# metronome.net
KiCad netlist of a schematic drawn in EAGLE
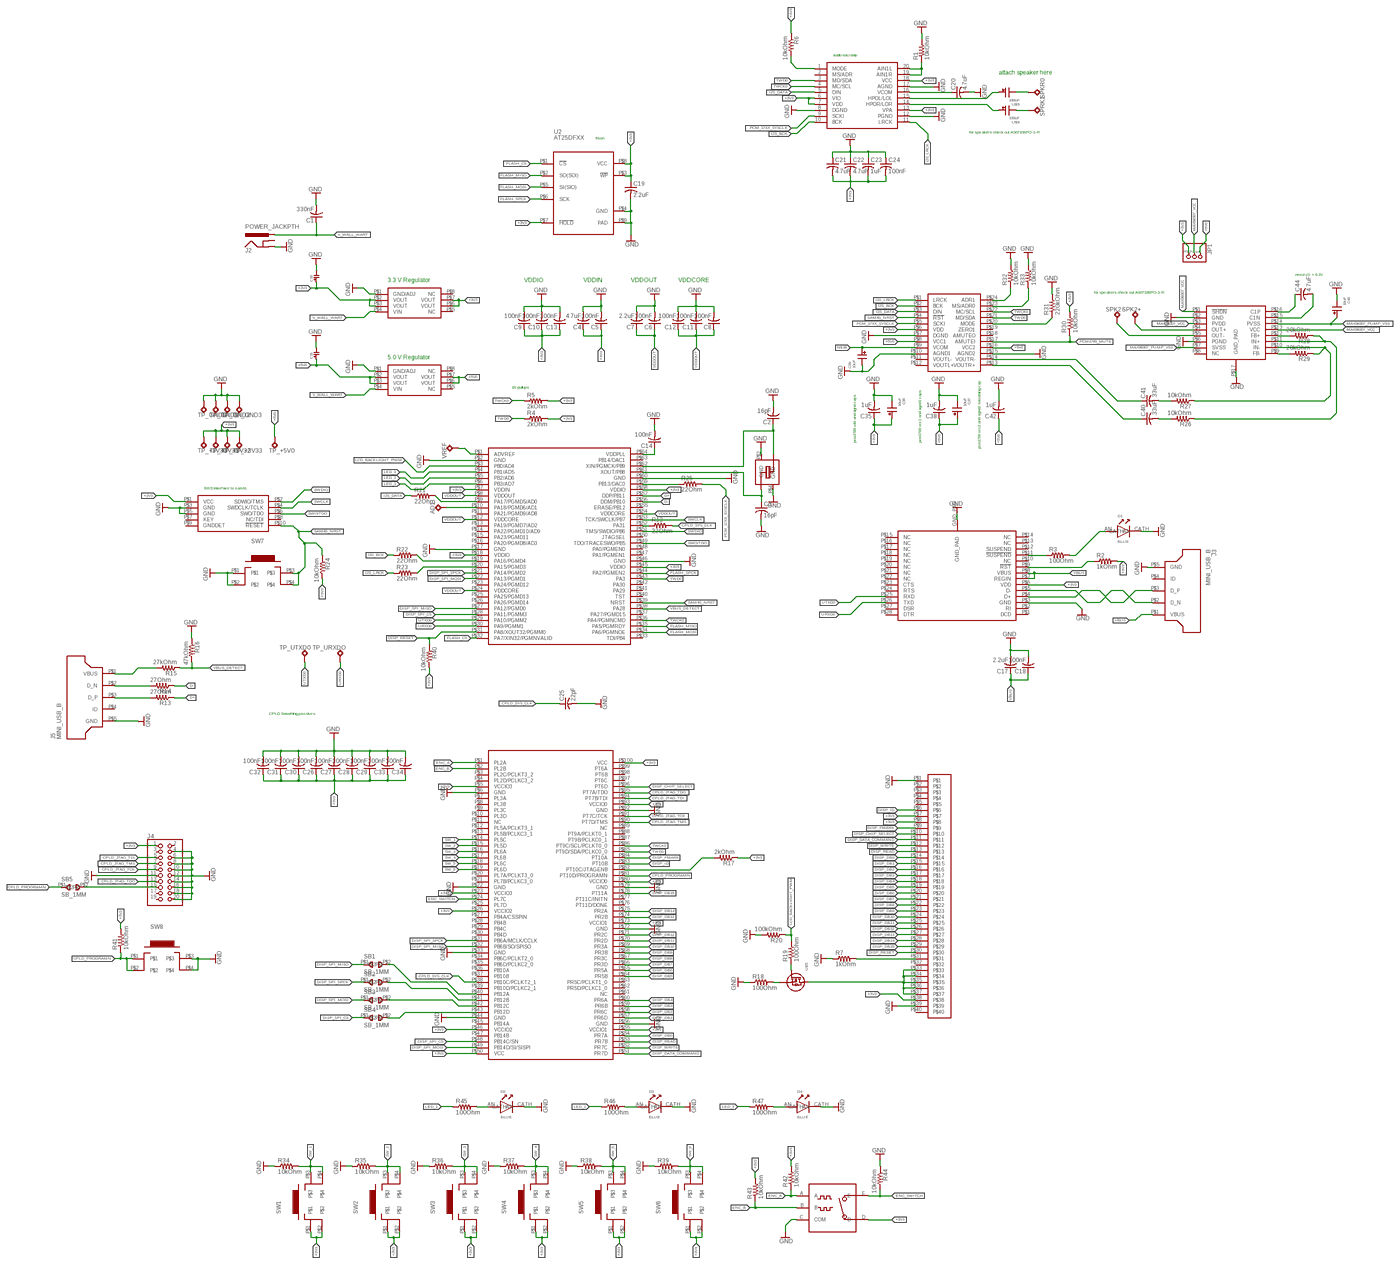
[diagram p0: schematic, sheet 1, overview]
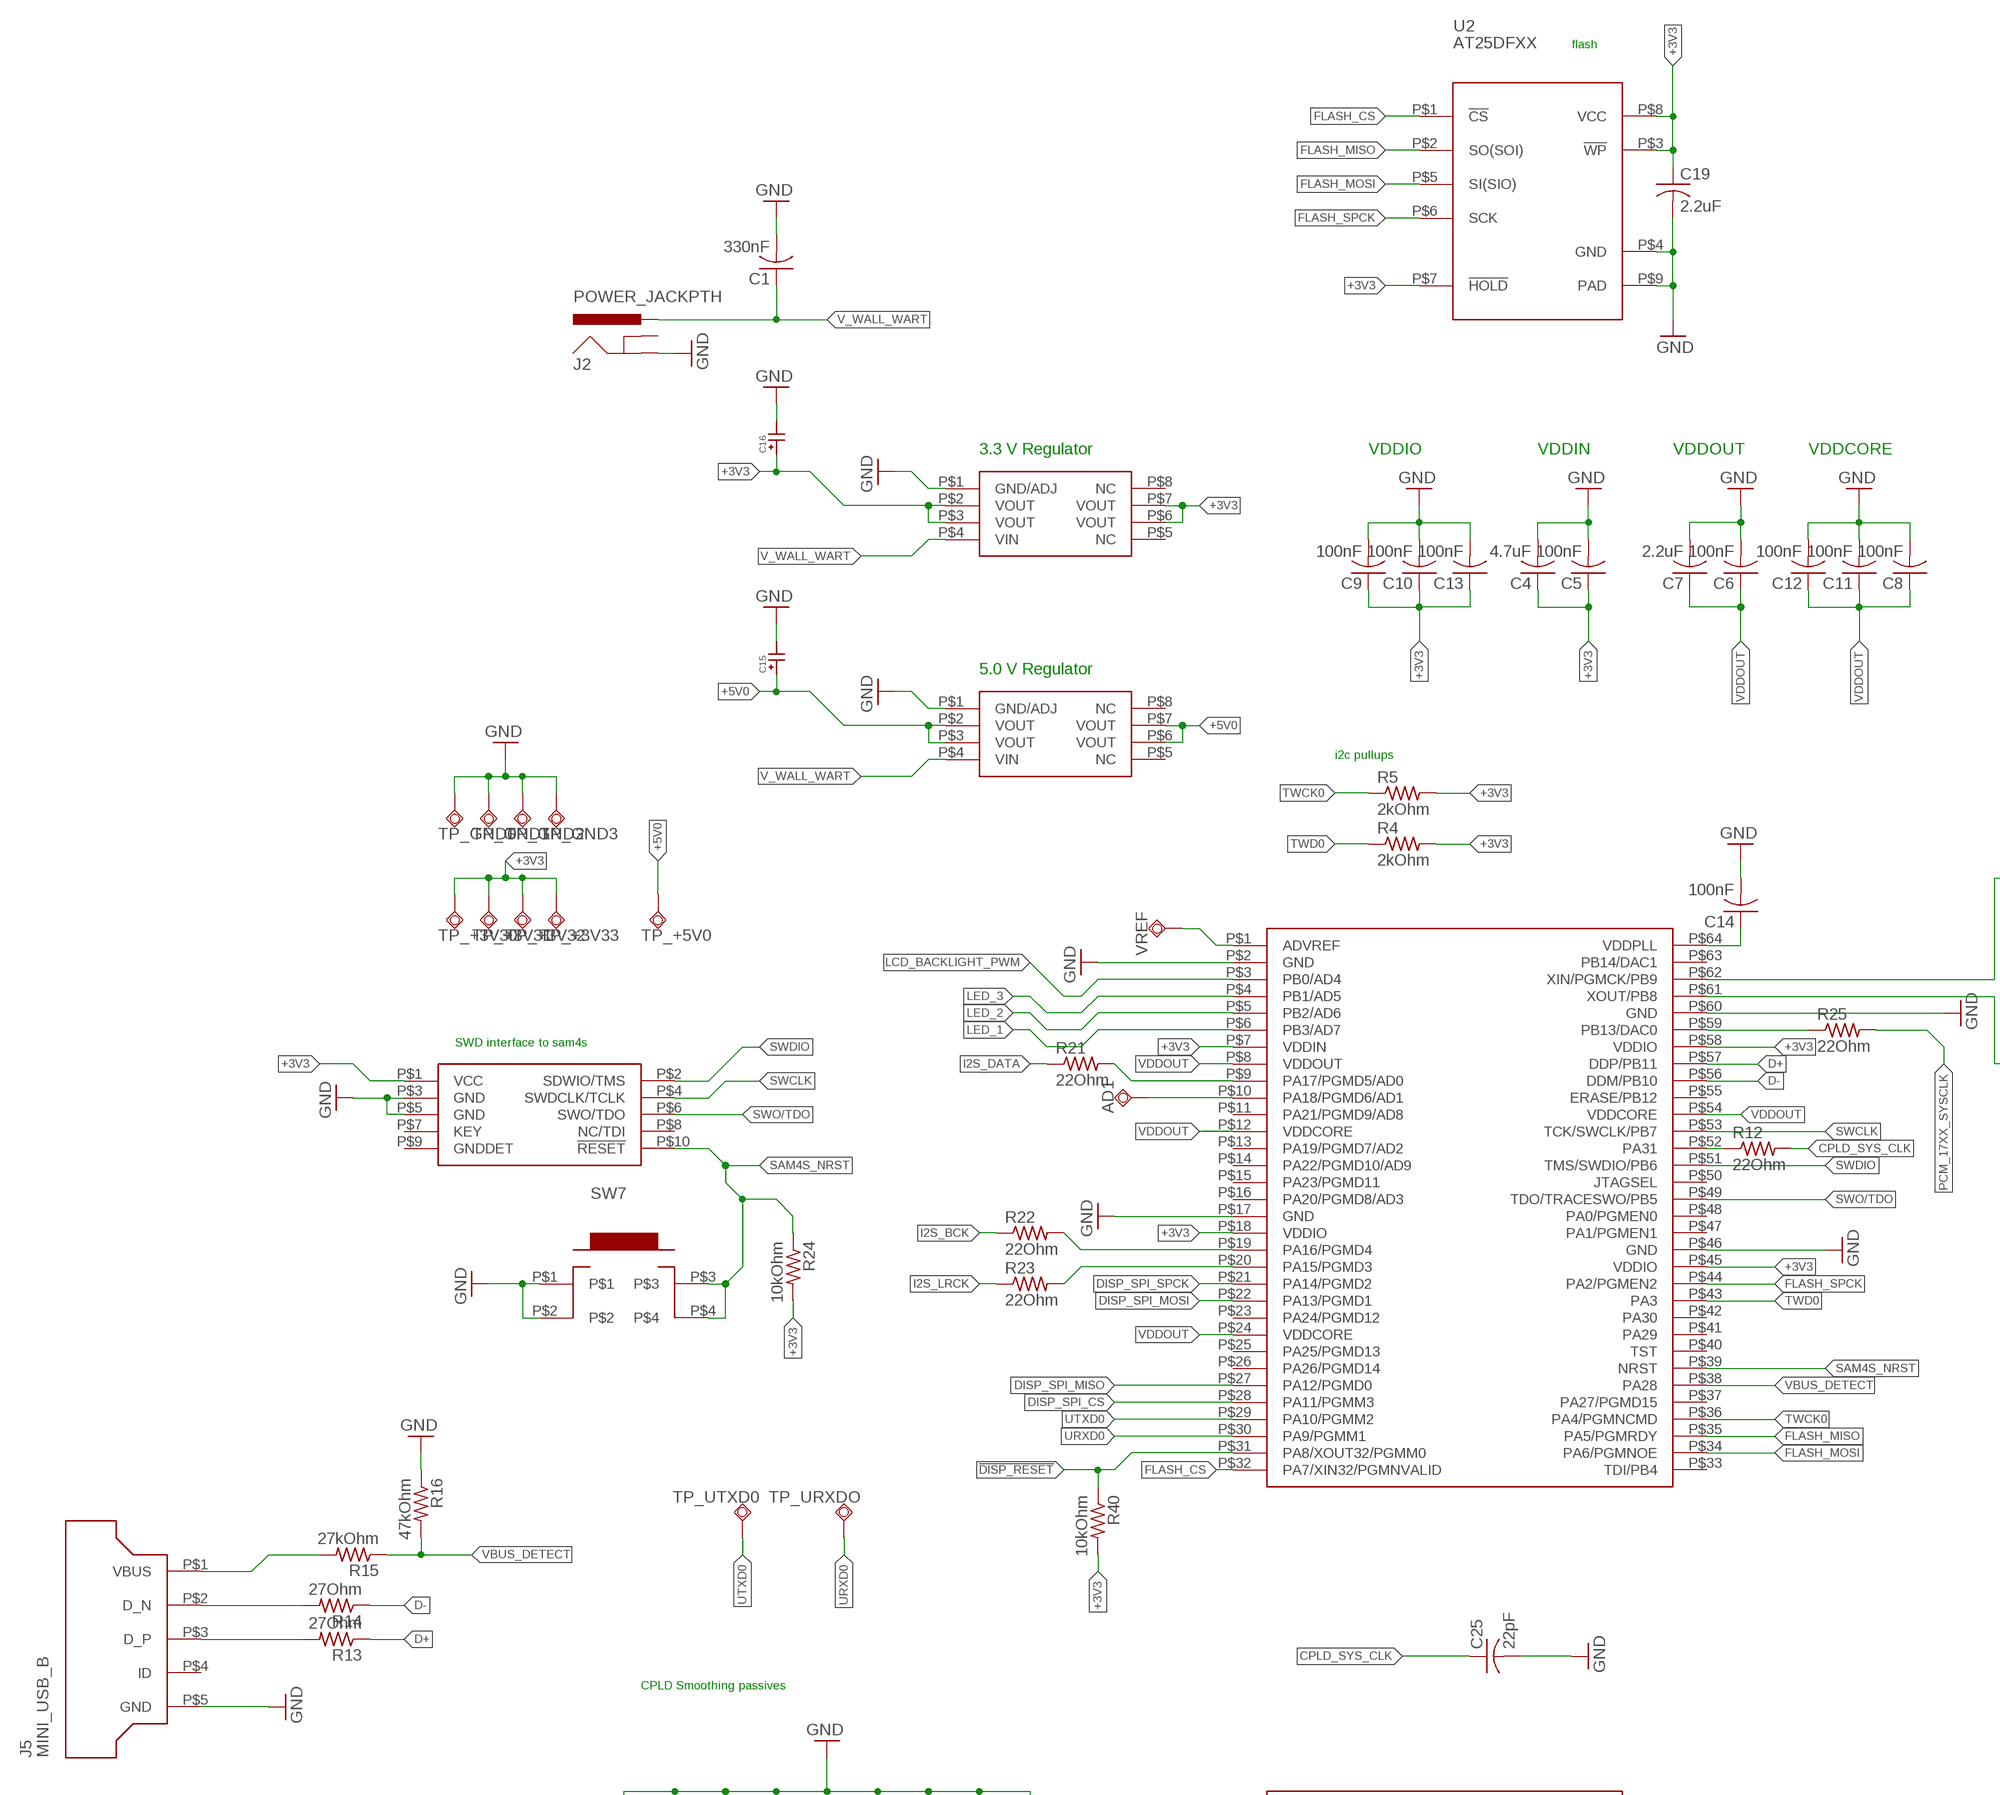
[diagram p1: schematic, sheet 1, part 1 of 4]
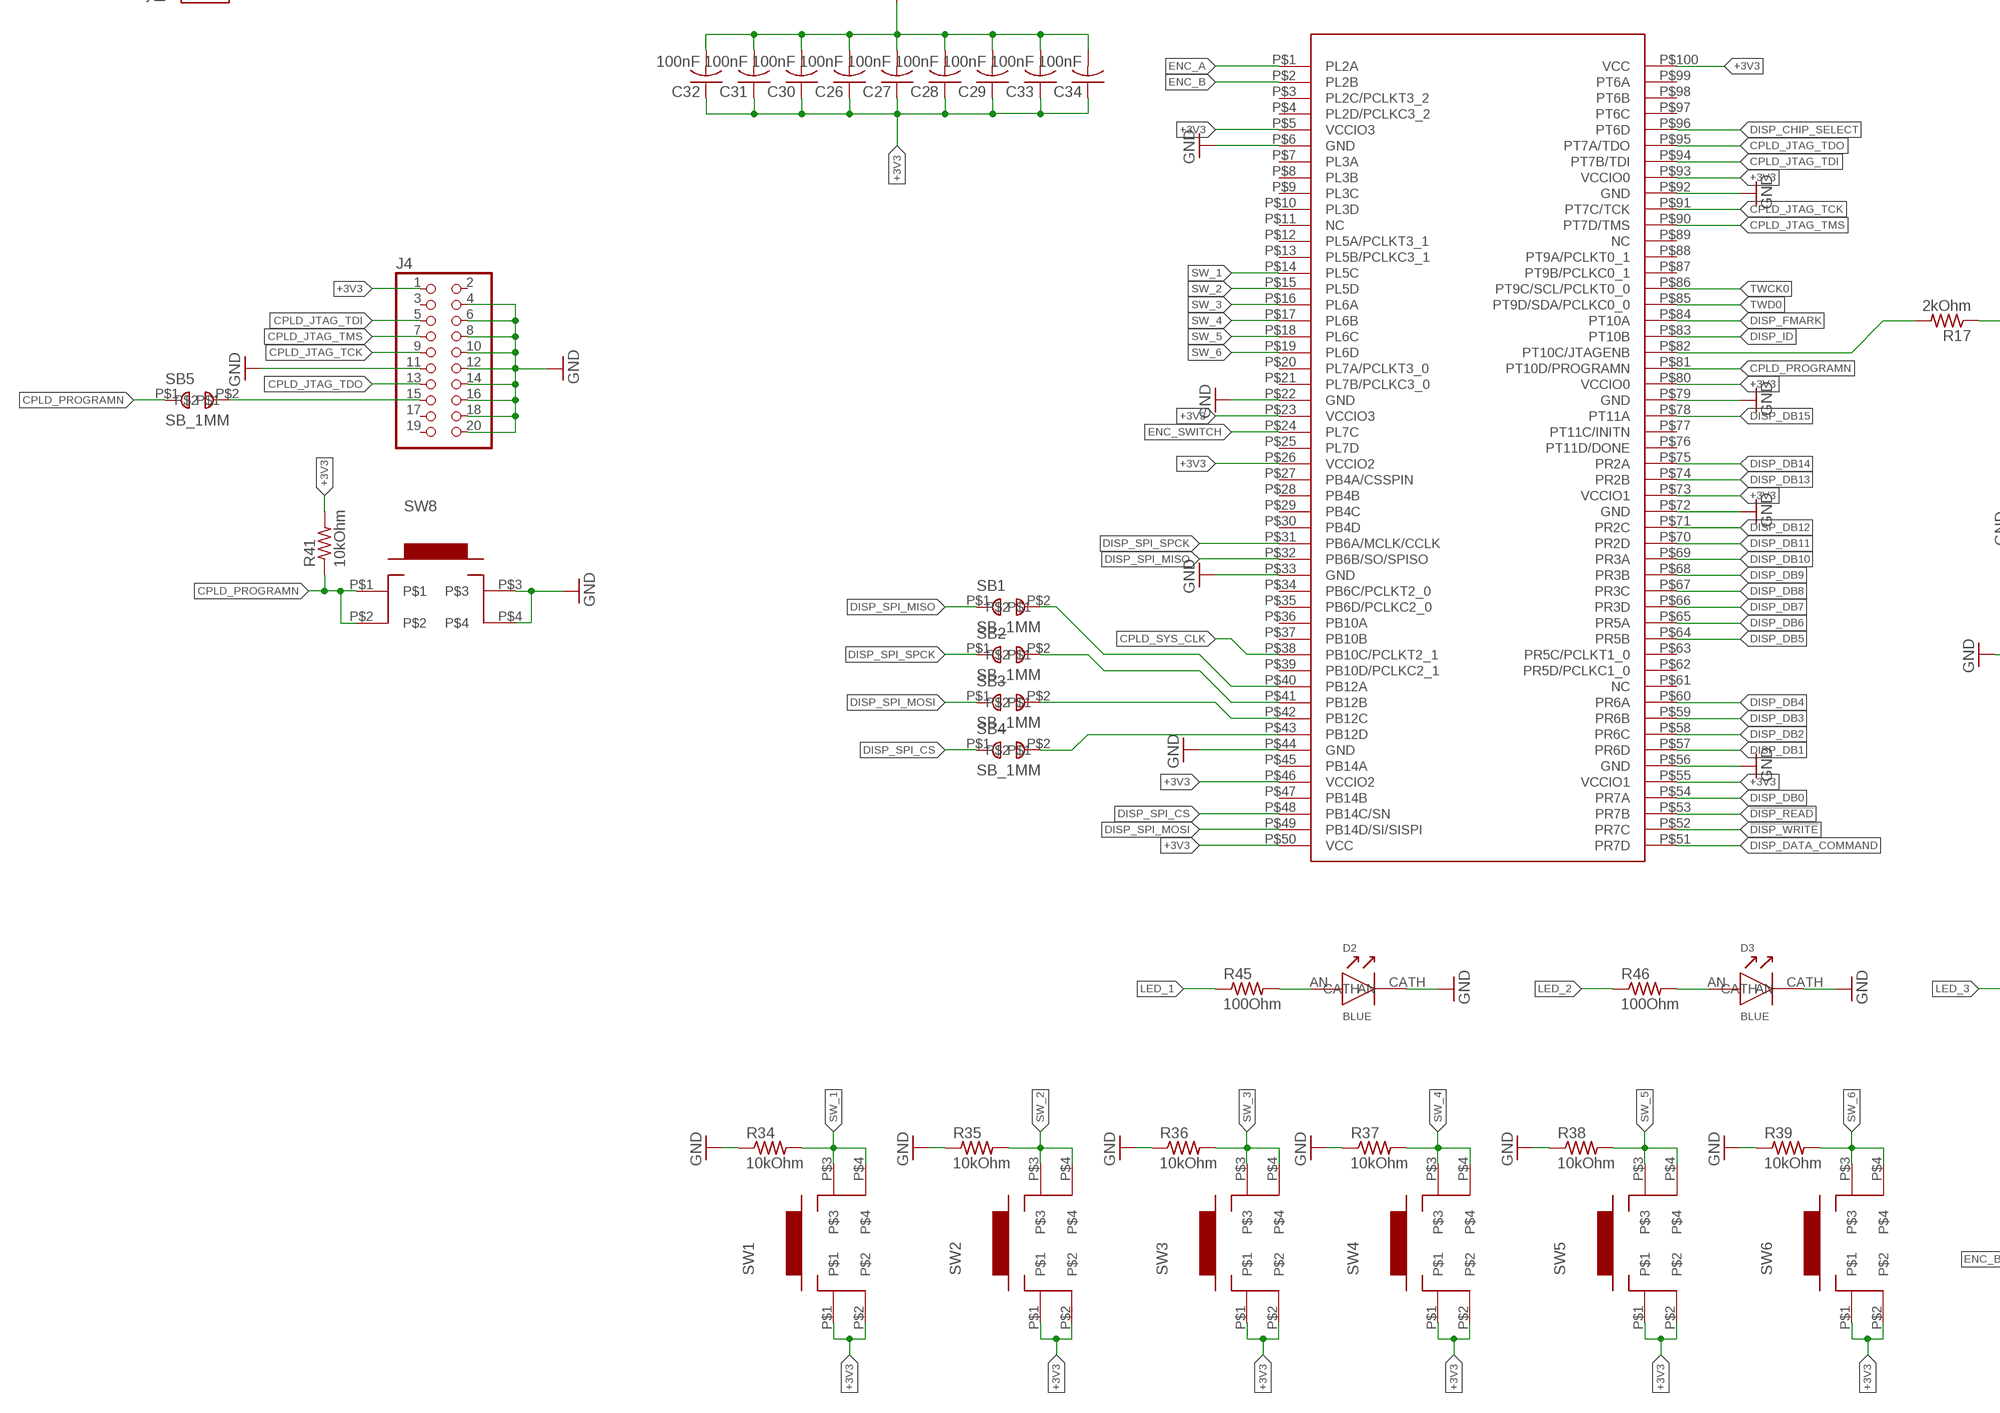
[diagram p2: schematic, sheet 1, part 2 of 4]
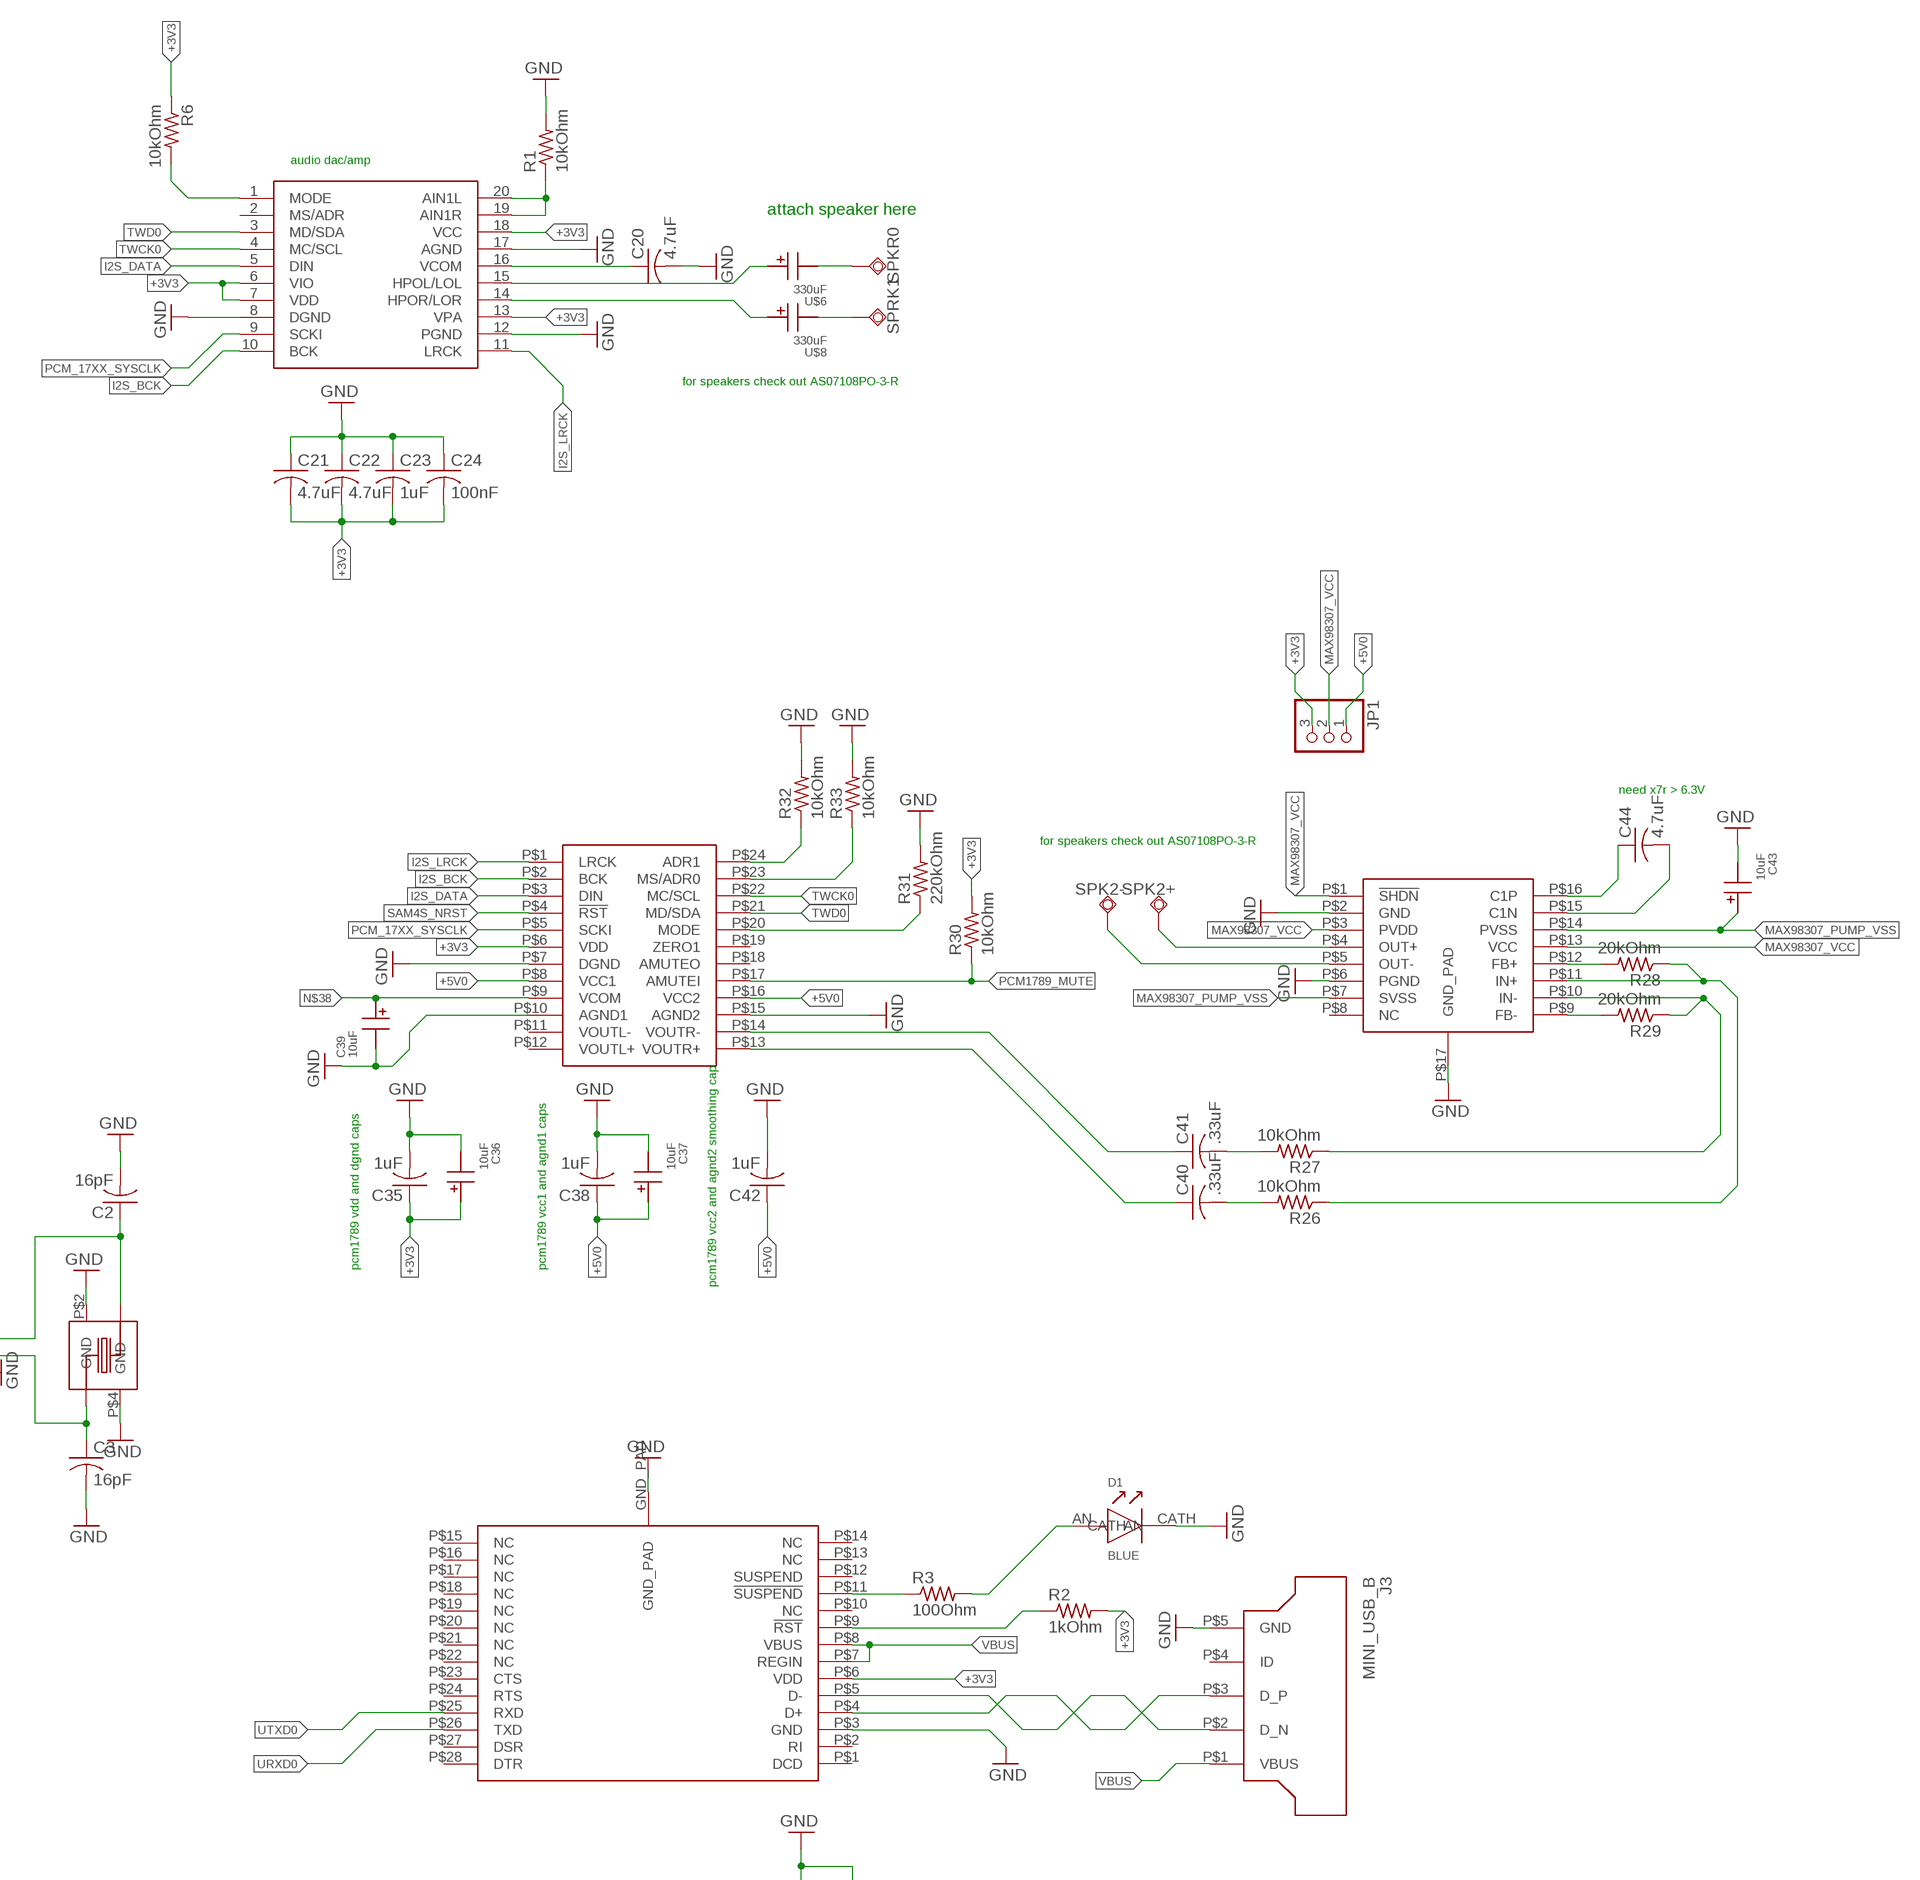
[diagram p3: schematic, sheet 1, part 3 of 4]
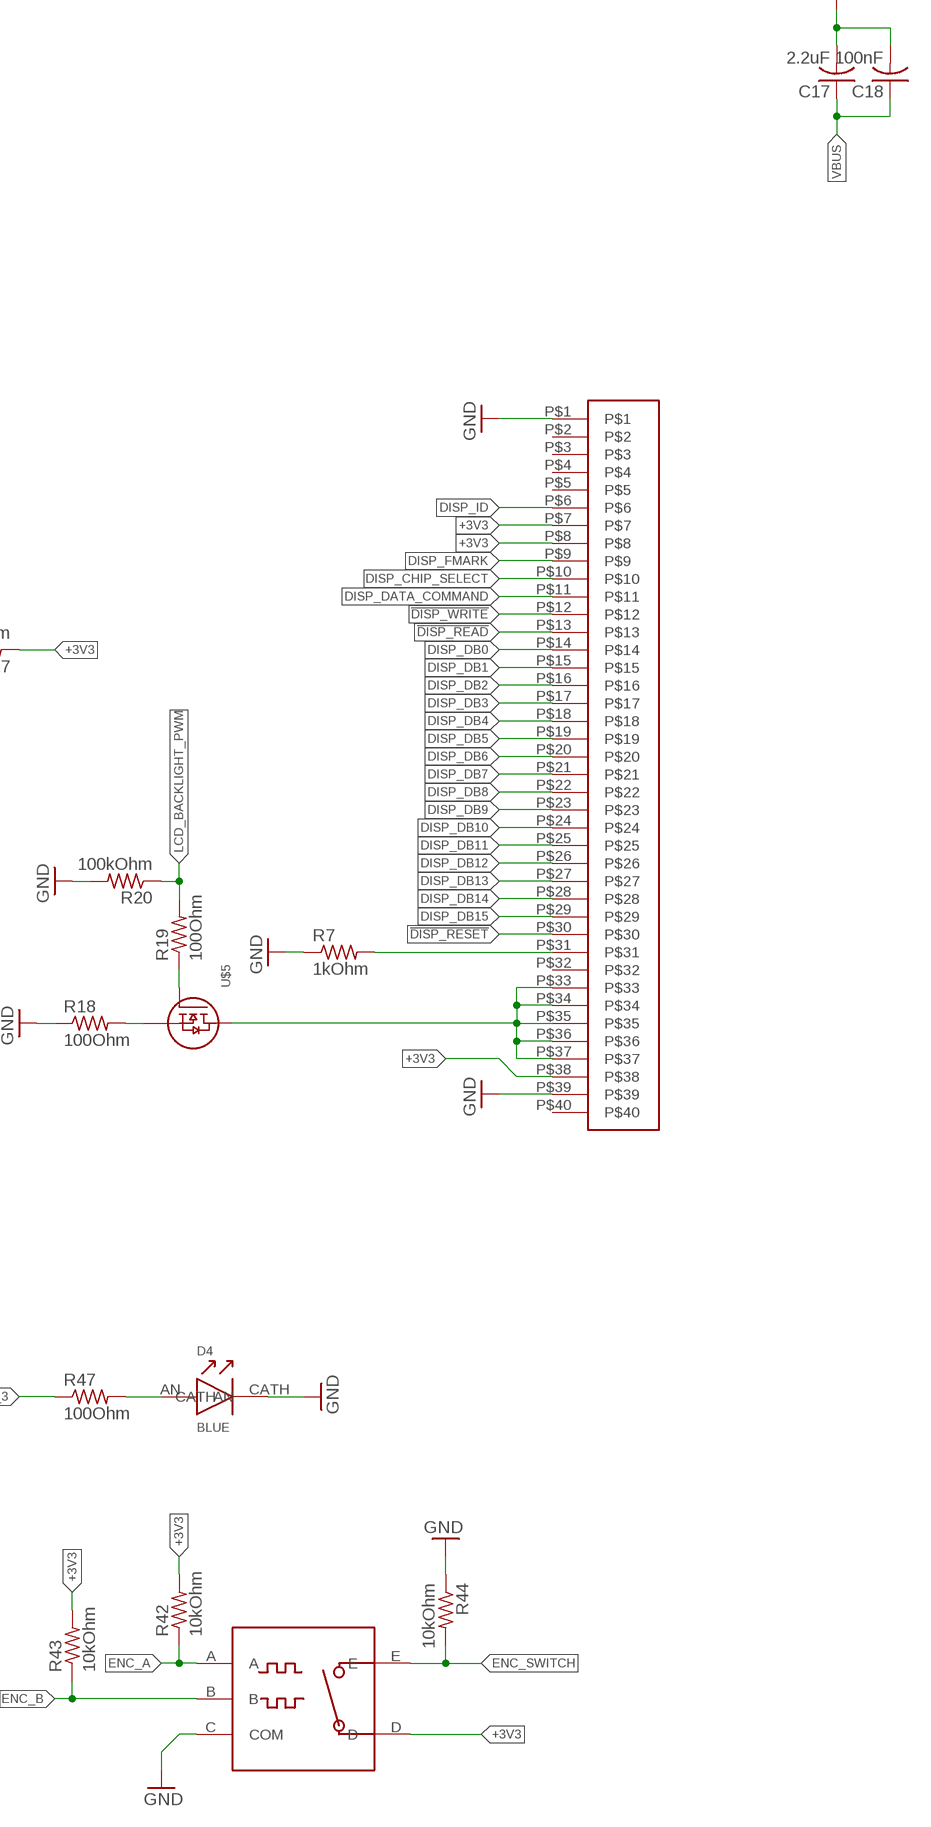
[diagram p4: schematic, sheet 1, part 4 of 4]

(export (version "E")
  (design (tool "Eeschema 10.0.6"))
  (components
    (comp (ref "3.3_V_REG")
      (value "MC33269D-3.3GOS-ND")
      (footprint "eagle-import:ON_SEMICONDUCTOR_MC33269")
      (libsource (lib "eagle-import") (part "MC33269D-3.3GOS-ND"))
    )
    (comp (ref "5.0_V_REG")
      (value "MC33269D-5.0GOS-ND")
      (footprint "eagle-import:ON_SEMICONDUCTOR_MC33269")
      (libsource (lib "eagle-import") (part "MC33269D-5.0GOS-ND"))
    )
    (comp (ref "AD1")
      (value "TPSQTP13SQ")
      (footprint "eagle-import:TP13SQ")
      (libsource (lib "eagle-import") (part "TPSQTP13SQ"))
    )
    (comp (ref "C1")
      (value "330nF")
      (footprint "eagle-import:C0402")
      (libsource (lib "eagle-import") (part "C-USC0402"))
    )
    (comp (ref "C2")
      (value "16pF")
      (footprint "eagle-import:C0402")
      (libsource (lib "eagle-import") (part "C-USC0402"))
    )
    (comp (ref "C3")
      (value "16pF")
      (footprint "eagle-import:C0402")
      (libsource (lib "eagle-import") (part "C-USC0402"))
    )
    (comp (ref "C4")
      (value "4.7uF")
      (footprint "eagle-import:C0603")
      (libsource (lib "eagle-import") (part "C-USC0603"))
    )
    (comp (ref "C5")
      (value "100nF")
      (footprint "eagle-import:C0402")
      (libsource (lib "eagle-import") (part "C-USC0402"))
    )
    (comp (ref "C6")
      (value "100nF")
      (footprint "eagle-import:C0402")
      (libsource (lib "eagle-import") (part "C-USC0402"))
    )
    (comp (ref "C7")
      (value "2.2uF")
      (footprint "eagle-import:C0603")
      (libsource (lib "eagle-import") (part "C-USC0603"))
    )
    (comp (ref "C8")
      (value "100nF")
      (footprint "eagle-import:C0402")
      (libsource (lib "eagle-import") (part "C-USC0402"))
    )
    (comp (ref "C9")
      (value "100nF")
      (footprint "eagle-import:C0402")
      (libsource (lib "eagle-import") (part "C-USC0402"))
    )
    (comp (ref "C10")
      (value "100nF")
      (footprint "eagle-import:C0402")
      (libsource (lib "eagle-import") (part "C-USC0402"))
    )
    (comp (ref "C11")
      (value "100nF")
      (footprint "eagle-import:C0402")
      (libsource (lib "eagle-import") (part "C-USC0402"))
    )
    (comp (ref "C12")
      (value "100nF")
      (footprint "eagle-import:C0402")
      (libsource (lib "eagle-import") (part "C-USC0402"))
    )
    (comp (ref "C13")
      (value "100nF")
      (footprint "eagle-import:C0402")
      (libsource (lib "eagle-import") (part "C-USC0402"))
    )
    (comp (ref "C14")
      (value "100nF")
      (footprint "eagle-import:C0402")
      (libsource (lib "eagle-import") (part "C-USC0402"))
    )
    (comp (ref "C15")
      (value "KEMET_T491A")
      (footprint "eagle-import:KEMET_T491A")
      (libsource (lib "eagle-import") (part "KEMET_T491A"))
    )
    (comp (ref "C16")
      (value "KEMET_T491A")
      (footprint "eagle-import:KEMET_T491A")
      (libsource (lib "eagle-import") (part "KEMET_T491A"))
    )
    (comp (ref "C17")
      (value "2.2uF")
      (footprint "eagle-import:C0603")
      (libsource (lib "eagle-import") (part "C-USC0603"))
    )
    (comp (ref "C18")
      (value "100nF")
      (footprint "eagle-import:C0402")
      (libsource (lib "eagle-import") (part "C-USC0402"))
    )
    (comp (ref "C19")
      (value "2.2uF")
      (footprint "eagle-import:C0603")
      (libsource (lib "eagle-import") (part "C-USC0603"))
    )
    (comp (ref "C20")
      (value "4.7uF")
      (footprint "eagle-import:C0402")
      (libsource (lib "eagle-import") (part "C-USC0402"))
    )
    (comp (ref "C21")
      (value "4.7uF")
      (footprint "eagle-import:C0402")
      (libsource (lib "eagle-import") (part "C-USC0402"))
    )
    (comp (ref "C22")
      (value "4.7uF")
      (footprint "eagle-import:C0402")
      (libsource (lib "eagle-import") (part "C-USC0402"))
    )
    (comp (ref "C23")
      (value "1uF")
      (footprint "eagle-import:C0402")
      (libsource (lib "eagle-import") (part "C-USC0402"))
    )
    (comp (ref "C24")
      (value "100nF")
      (footprint "eagle-import:C0402")
      (libsource (lib "eagle-import") (part "C-USC0402"))
    )
    (comp (ref "C25")
      (value "22pF")
      (footprint "eagle-import:C0402")
      (libsource (lib "eagle-import") (part "C-USC0402"))
    )
    (comp (ref "C26")
      (value "100nF")
      (footprint "eagle-import:C0402")
      (libsource (lib "eagle-import") (part "C-USC0402"))
    )
    (comp (ref "C27")
      (value "100nF")
      (footprint "eagle-import:C0402")
      (libsource (lib "eagle-import") (part "C-USC0402"))
    )
    (comp (ref "C28")
      (value "100nF")
      (footprint "eagle-import:C0402")
      (libsource (lib "eagle-import") (part "C-USC0402"))
    )
    (comp (ref "C29")
      (value "100nF")
      (footprint "eagle-import:C0402")
      (libsource (lib "eagle-import") (part "C-USC0402"))
    )
    (comp (ref "C30")
      (value "100nF")
      (footprint "eagle-import:C0402")
      (libsource (lib "eagle-import") (part "C-USC0402"))
    )
    (comp (ref "C31")
      (value "100nF")
      (footprint "eagle-import:C0402")
      (libsource (lib "eagle-import") (part "C-USC0402"))
    )
    (comp (ref "C32")
      (value "100nF")
      (footprint "eagle-import:C0402")
      (libsource (lib "eagle-import") (part "C-USC0402"))
    )
    (comp (ref "C33")
      (value "100nF")
      (footprint "eagle-import:C0402")
      (libsource (lib "eagle-import") (part "C-USC0402"))
    )
    (comp (ref "C34")
      (value "100nF")
      (footprint "eagle-import:C0402")
      (libsource (lib "eagle-import") (part "C-USC0402"))
    )
    (comp (ref "C35")
      (value "1uF")
      (footprint "eagle-import:C0402")
      (libsource (lib "eagle-import") (part "C-USC0402"))
    )
    (comp (ref "C36")
      (value "10uF")
      (footprint "eagle-import:PANASONIC_EEEHB100AR")
      (libsource (lib "eagle-import") (part "PANASONIC_HB1C100AR"))
    )
    (comp (ref "C37")
      (value "10uF")
      (footprint "eagle-import:PANASONIC_EEEHB100AR")
      (libsource (lib "eagle-import") (part "PANASONIC_HB1C100AR"))
    )
    (comp (ref "C38")
      (value "1uF")
      (footprint "eagle-import:C0402")
      (libsource (lib "eagle-import") (part "C-USC0402"))
    )
    (comp (ref "C39")
      (value "10uF")
      (footprint "eagle-import:PANASONIC_EEEHB100AR")
      (libsource (lib "eagle-import") (part "PANASONIC_HB1C100AR"))
    )
    (comp (ref "C40")
      (value ".33uF")
      (footprint "eagle-import:C0402")
      (libsource (lib "eagle-import") (part "C-USC0402"))
    )
    (comp (ref "C41")
      (value ".33uF")
      (footprint "eagle-import:C0402")
      (libsource (lib "eagle-import") (part "C-USC0402"))
    )
    (comp (ref "C42")
      (value "1uF")
      (footprint "eagle-import:C0402")
      (libsource (lib "eagle-import") (part "C-USC0402"))
    )
    (comp (ref "C43")
      (value "10uF")
      (footprint "eagle-import:PANASONIC_EEEHB100AR")
      (libsource (lib "eagle-import") (part "PANASONIC_HB1C100AR"))
    )
    (comp (ref "C44")
      (value "4.7uF")
      (footprint "eagle-import:C0603")
      (libsource (lib "eagle-import") (part "C-USC0603"))
    )
    (comp (ref "D1")
      (value "BLUE")
      (footprint "eagle-import:D0603")
      (libsource (lib "eagle-import") (part "LED0603"))
    )
    (comp (ref "D2")
      (value "BLUE")
      (footprint "eagle-import:D0603")
      (libsource (lib "eagle-import") (part "LED0603"))
    )
    (comp (ref "D3")
      (value "BLUE")
      (footprint "eagle-import:D0603")
      (libsource (lib "eagle-import") (part "LED0603"))
    )
    (comp (ref "D4")
      (value "BLUE")
      (footprint "eagle-import:D0603")
      (libsource (lib "eagle-import") (part "LED0603"))
    )
    (comp (ref "J1")
      (value "FCI_CORTEX_SWD_CONNECTOR")
      (footprint "eagle-import:FCI_10_PIN_SMD_0.5")
      (libsource (lib "eagle-import") (part "FCI_CORTEX_SWD_CONNECTOR"))
    )
    (comp (ref "J2")
      (value "POWER_JACKPTH")
      (footprint "eagle-import:POWER_JACK_PTH")
      (libsource (lib "eagle-import") (part "POWER_JACKPTH"))
    )
    (comp (ref "J3")
      (value "MINI_USB_B")
      (footprint "eagle-import:UX60SC-MB-5ST")
      (libsource (lib "eagle-import") (part "MINI_USB_B"))
    )
    (comp (ref "J4")
      (value "PINHD-2X10")
      (footprint "eagle-import:2X10")
      (libsource (lib "eagle-import") (part "PINHD-2X10"))
    )
    (comp (ref "J5")
      (value "MINI_USB_B")
      (footprint "eagle-import:UX60SC-MB-5ST")
      (libsource (lib "eagle-import") (part "MINI_USB_B"))
    )
    (comp (ref "JP1")
      (value "PINHD-1X3")
      (footprint "eagle-import:1X03")
      (libsource (lib "eagle-import") (part "PINHD-1X3"))
    )
    (comp (ref "R1")
      (value "10kOhm")
      (footprint "eagle-import:R0402")
      (libsource (lib "eagle-import") (part "R-US_R0402"))
    )
    (comp (ref "R2")
      (value "1kOhm")
      (footprint "eagle-import:R0402")
      (libsource (lib "eagle-import") (part "R-US_R0402"))
    )
    (comp (ref "R3")
      (value "100Ohm")
      (footprint "eagle-import:R0402")
      (libsource (lib "eagle-import") (part "R-US_R0402"))
    )
    (comp (ref "R4")
      (value "2kOhm")
      (footprint "eagle-import:R0402")
      (libsource (lib "eagle-import") (part "R-US_R0402"))
    )
    (comp (ref "R5")
      (value "2kOhm")
      (footprint "eagle-import:R0402")
      (libsource (lib "eagle-import") (part "R-US_R0402"))
    )
    (comp (ref "R6")
      (value "10kOhm")
      (footprint "eagle-import:R0402")
      (libsource (lib "eagle-import") (part "R-US_R0402"))
    )
    (comp (ref "R7")
      (value "1kOhm")
      (footprint "eagle-import:R0402")
      (libsource (lib "eagle-import") (part "R-US_R0402"))
    )
    (comp (ref "R12")
      (value "22Ohm")
      (footprint "eagle-import:R0402")
      (libsource (lib "eagle-import") (part "R-US_R0402"))
    )
    (comp (ref "R13")
      (value "27Ohm")
      (footprint "eagle-import:R0402")
      (libsource (lib "eagle-import") (part "R-US_R0402"))
    )
    (comp (ref "R14")
      (value "27Ohm")
      (footprint "eagle-import:R0402")
      (libsource (lib "eagle-import") (part "R-US_R0402"))
    )
    (comp (ref "R15")
      (value "27kOhm")
      (footprint "eagle-import:R0402")
      (libsource (lib "eagle-import") (part "R-US_R0402"))
    )
    (comp (ref "R16")
      (value "47kOhm")
      (footprint "eagle-import:R0402")
      (libsource (lib "eagle-import") (part "R-US_R0402"))
    )
    (comp (ref "R17")
      (value "2kOhm")
      (footprint "eagle-import:R0402")
      (libsource (lib "eagle-import") (part "R-US_R0402"))
    )
    (comp (ref "R18")
      (value "100Ohm")
      (footprint "eagle-import:R0402")
      (libsource (lib "eagle-import") (part "R-US_R0402"))
    )
    (comp (ref "R19")
      (value "100Ohm")
      (footprint "eagle-import:R0402")
      (libsource (lib "eagle-import") (part "R-US_R0402"))
    )
    (comp (ref "R20")
      (value "100kOhm")
      (footprint "eagle-import:R0402")
      (libsource (lib "eagle-import") (part "R-US_R0402"))
    )
    (comp (ref "R21")
      (value "22Ohm")
      (footprint "eagle-import:R0402")
      (libsource (lib "eagle-import") (part "R-US_R0402"))
    )
    (comp (ref "R22")
      (value "22Ohm")
      (footprint "eagle-import:R0402")
      (libsource (lib "eagle-import") (part "R-US_R0402"))
    )
    (comp (ref "R23")
      (value "22Ohm")
      (footprint "eagle-import:R0402")
      (libsource (lib "eagle-import") (part "R-US_R0402"))
    )
    (comp (ref "R24")
      (value "10kOhm")
      (footprint "eagle-import:R0402")
      (libsource (lib "eagle-import") (part "R-US_R0402"))
    )
    (comp (ref "R25")
      (value "22Ohm")
      (footprint "eagle-import:R0402")
      (libsource (lib "eagle-import") (part "R-US_R0402"))
    )
    (comp (ref "R26")
      (value "10kOhm")
      (footprint "eagle-import:R0402")
      (libsource (lib "eagle-import") (part "R-US_R0402"))
    )
    (comp (ref "R27")
      (value "10kOhm")
      (footprint "eagle-import:R0402")
      (libsource (lib "eagle-import") (part "R-US_R0402"))
    )
    (comp (ref "R28")
      (value "20kOhm")
      (footprint "eagle-import:R0402")
      (libsource (lib "eagle-import") (part "R-US_R0402"))
    )
    (comp (ref "R29")
      (value "20kOhm")
      (footprint "eagle-import:R0402")
      (libsource (lib "eagle-import") (part "R-US_R0402"))
    )
    (comp (ref "R30")
      (value "10kOhm")
      (footprint "eagle-import:R0402")
      (libsource (lib "eagle-import") (part "R-US_R0402"))
    )
    (comp (ref "R31")
      (value "220kOhm")
      (footprint "eagle-import:R0402")
      (libsource (lib "eagle-import") (part "R-US_R0402"))
    )
    (comp (ref "R32")
      (value "10kOhm")
      (footprint "eagle-import:R0402")
      (libsource (lib "eagle-import") (part "R-US_R0402"))
    )
    (comp (ref "R33")
      (value "10kOhm")
      (footprint "eagle-import:R0402")
      (libsource (lib "eagle-import") (part "R-US_R0402"))
    )
    (comp (ref "R34")
      (value "10kOhm")
      (footprint "eagle-import:R0402")
      (libsource (lib "eagle-import") (part "R-US_R0402"))
    )
    (comp (ref "R35")
      (value "10kOhm")
      (footprint "eagle-import:R0402")
      (libsource (lib "eagle-import") (part "R-US_R0402"))
    )
    (comp (ref "R36")
      (value "10kOhm")
      (footprint "eagle-import:R0402")
      (libsource (lib "eagle-import") (part "R-US_R0402"))
    )
    (comp (ref "R37")
      (value "10kOhm")
      (footprint "eagle-import:R0402")
      (libsource (lib "eagle-import") (part "R-US_R0402"))
    )
    (comp (ref "R38")
      (value "10kOhm")
      (footprint "eagle-import:R0402")
      (libsource (lib "eagle-import") (part "R-US_R0402"))
    )
    (comp (ref "R39")
      (value "10kOhm")
      (footprint "eagle-import:R0402")
      (libsource (lib "eagle-import") (part "R-US_R0402"))
    )
    (comp (ref "R40")
      (value "10kOhm")
      (footprint "eagle-import:R0402")
      (libsource (lib "eagle-import") (part "R-US_R0402"))
    )
    (comp (ref "R41")
      (value "10kOhm")
      (footprint "eagle-import:R0402")
      (libsource (lib "eagle-import") (part "R-US_R0402"))
    )
    (comp (ref "R42")
      (value "10kOhm")
      (footprint "eagle-import:R0402")
      (libsource (lib "eagle-import") (part "R-US_R0402"))
    )
    (comp (ref "R43")
      (value "10kOhm")
      (footprint "eagle-import:R0402")
      (libsource (lib "eagle-import") (part "R-US_R0402"))
    )
    (comp (ref "R44")
      (value "10kOhm")
      (footprint "eagle-import:R0402")
      (libsource (lib "eagle-import") (part "R-US_R0402"))
    )
    (comp (ref "R45")
      (value "100Ohm")
      (footprint "eagle-import:R0402")
      (libsource (lib "eagle-import") (part "R-US_R0402"))
    )
    (comp (ref "R46")
      (value "100Ohm")
      (footprint "eagle-import:R0402")
      (libsource (lib "eagle-import") (part "R-US_R0402"))
    )
    (comp (ref "R47")
      (value "100Ohm")
      (footprint "eagle-import:R0402")
      (libsource (lib "eagle-import") (part "R-US_R0402"))
    )
    (comp (ref "SB1")
      (value "SB_1MM")
      (footprint "eagle-import:SB_1MM")
      (libsource (lib "eagle-import") (part "SB_1MM"))
    )
    (comp (ref "SB2")
      (value "SB_1MM")
      (footprint "eagle-import:SB_1MM")
      (libsource (lib "eagle-import") (part "SB_1MM"))
    )
    (comp (ref "SB3")
      (value "SB_1MM")
      (footprint "eagle-import:SB_1MM")
      (libsource (lib "eagle-import") (part "SB_1MM"))
    )
    (comp (ref "SB4")
      (value "SB_1MM")
      (footprint "eagle-import:SB_1MM")
      (libsource (lib "eagle-import") (part "SB_1MM"))
    )
    (comp (ref "SB5")
      (value "SB_1MM")
      (footprint "eagle-import:SB_1MM")
      (libsource (lib "eagle-import") (part "SB_1MM"))
    )
    (comp (ref "SPK2+")
      (value "TPSQTP20SQ")
      (footprint "eagle-import:TP20SQ")
      (libsource (lib "eagle-import") (part "TPSQTP20SQ"))
    )
    (comp (ref "SPK2-")
      (value "TPSQTP20SQ")
      (footprint "eagle-import:TP20SQ")
      (libsource (lib "eagle-import") (part "TPSQTP20SQ"))
    )
    (comp (ref "SPKR0")
      (value "TPSQTP20SQ")
      (footprint "eagle-import:TP20SQ")
      (libsource (lib "eagle-import") (part "TPSQTP20SQ"))
    )
    (comp (ref "SPRK1")
      (value "TPSQTP20SQ")
      (footprint "eagle-import:TP20SQ")
      (libsource (lib "eagle-import") (part "TPSQTP20SQ"))
    )
    (comp (ref "SW1")
      (value "FSMJSMA")
      (footprint "eagle-import:FSMJSMA")
      (libsource (lib "eagle-import") (part "FSMJSMA"))
    )
    (comp (ref "SW2")
      (value "FSMJSMA")
      (footprint "eagle-import:FSMJSMA")
      (libsource (lib "eagle-import") (part "FSMJSMA"))
    )
    (comp (ref "SW3")
      (value "FSMJSMA")
      (footprint "eagle-import:FSMJSMA")
      (libsource (lib "eagle-import") (part "FSMJSMA"))
    )
    (comp (ref "SW4")
      (value "FSMJSMA")
      (footprint "eagle-import:FSMJSMA")
      (libsource (lib "eagle-import") (part "FSMJSMA"))
    )
    (comp (ref "SW5")
      (value "FSMJSMA")
      (footprint "eagle-import:FSMJSMA")
      (libsource (lib "eagle-import") (part "FSMJSMA"))
    )
    (comp (ref "SW6")
      (value "FSMJSMA")
      (footprint "eagle-import:FSMJSMA")
      (libsource (lib "eagle-import") (part "FSMJSMA"))
    )
    (comp (ref "SW7")
      (value "FSMJSMA")
      (footprint "eagle-import:FSMJSMA")
      (libsource (lib "eagle-import") (part "FSMJSMA"))
    )
    (comp (ref "SW8")
      (value "FSMJSMA")
      (footprint "eagle-import:FSMJSMA")
      (libsource (lib "eagle-import") (part "FSMJSMA"))
    )
    (comp (ref "TP_+3V30")
      (value "TPSQTP20SQ")
      (footprint "eagle-import:TP20SQ")
      (libsource (lib "eagle-import") (part "TPSQTP20SQ"))
    )
    (comp (ref "TP_+3V31")
      (value "TPSQTP20SQ")
      (footprint "eagle-import:TP20SQ")
      (libsource (lib "eagle-import") (part "TPSQTP20SQ"))
    )
    (comp (ref "TP_+3V32")
      (value "TPSQTP20SQ")
      (footprint "eagle-import:TP20SQ")
      (libsource (lib "eagle-import") (part "TPSQTP20SQ"))
    )
    (comp (ref "TP_+3V33")
      (value "TPSQTP20SQ")
      (footprint "eagle-import:TP20SQ")
      (libsource (lib "eagle-import") (part "TPSQTP20SQ"))
    )
    (comp (ref "TP_+5V0")
      (value "TPSQTP20SQ")
      (footprint "eagle-import:TP20SQ")
      (libsource (lib "eagle-import") (part "TPSQTP20SQ"))
    )
    (comp (ref "TP_GND0")
      (value "TPSQTP20SQ")
      (footprint "eagle-import:TP20SQ")
      (libsource (lib "eagle-import") (part "TPSQTP20SQ"))
    )
    (comp (ref "TP_GND1")
      (value "TPSQTP20SQ")
      (footprint "eagle-import:TP20SQ")
      (libsource (lib "eagle-import") (part "TPSQTP20SQ"))
    )
    (comp (ref "TP_GND2")
      (value "TPSQTP20SQ")
      (footprint "eagle-import:TP20SQ")
      (libsource (lib "eagle-import") (part "TPSQTP20SQ"))
    )
    (comp (ref "TP_GND3")
      (value "TPSQTP20SQ")
      (footprint "eagle-import:TP20SQ")
      (libsource (lib "eagle-import") (part "TPSQTP20SQ"))
    )
    (comp (ref "TP_URXDO")
      (value "TPSQTP20SQ")
      (footprint "eagle-import:TP20SQ")
      (libsource (lib "eagle-import") (part "TPSQTP20SQ"))
    )
    (comp (ref "TP_UTXD0")
      (value "TPSQTP20SQ")
      (footprint "eagle-import:TP20SQ")
      (libsource (lib "eagle-import") (part "TPSQTP20SQ"))
    )
    (comp (ref "U$1")
      (value "LATTICE_LCMXO2-640HC-4TG100C")
      (footprint "eagle-import:LATTICE_MACHXO_TQFP100")
      (libsource (lib "eagle-import") (part "LATTICE_LCMXO2-640HC-4TG100C"))
    )
    (comp (ref "U$2")
      (value "TI_PCM1774")
      (footprint "eagle-import:TI_QFN_20")
      (libsource (lib "eagle-import") (part "TI_PCM1774"))
    )
    (comp (ref "U$3")
      (value "ECS_ECS-120-20-33-CKM-TR")
      (footprint "eagle-import:ECS_ECX-32")
      (libsource (lib "eagle-import") (part "ECS_ECS-120-20-33-CKM-TR"))
    )
    (comp (ref "U$4")
      (value "40_PIN_MOLEX_FFC")
      (footprint "eagle-import:40_PIN_MOLEX_FFC")
      (libsource (lib "eagle-import") (part "40_PIN_MOLEX_FFC"))
    )
    (comp (ref "U$5")
      (value "DIODES_INCORPORATED_2N7002-7-F")
      (footprint "eagle-import:DIODES_INCORPORATED_SOT23")
      (libsource (lib "eagle-import") (part "DIODES_INCORPORATED_2N7002-7-F"))
    )
    (comp (ref "U$6")
      (value "330uF")
      (footprint "eagle-import:PANASONIC_EEEFT0JXXX")
      (libsource (lib "eagle-import") (part "PANASONIC_EEEFT0JXXX"))
    )
    (comp (ref "U$7")
      (value "SILABS_CP2102")
      (footprint "eagle-import:SILABS_QFN28")
      (libsource (lib "eagle-import") (part "SILABS_CP2102"))
    )
    (comp (ref "U$8")
      (value "330uF")
      (footprint "eagle-import:PANASONIC_EEEFT0JXXX")
      (libsource (lib "eagle-import") (part "PANASONIC_EEEFT0JXXX"))
    )
    (comp (ref "U$9")
      (value "TI_PCM1789")
      (footprint "eagle-import:TI_PW_TSSOP_24")
      (libsource (lib "eagle-import") (part "TI_PCM1789"))
    )
    (comp (ref "U$10")
      (value "MAXIM_MAX_98307")
      (footprint "eagle-import:MAXIM_16_TQFN_T1633-5")
      (libsource (lib "eagle-import") (part "MAXIM_MAX_98307"))
    )
    (comp (ref "U$11")
      (value "BOURNS_PEC16-4215F-S0024")
      (footprint "eagle-import:BOURNS_PEC16-4XXXF-SXXXX")
      (libsource (lib "eagle-import") (part "BOURNS_PEC16-4215F-S0024"))
    )
    (comp (ref "U1")
      (value "ATSAMD4S2BA-AU")
      (footprint "eagle-import:ATMEL_10X10_QFP_64")
      (libsource (lib "eagle-import") (part "ATSAMD4S2BA-AU"))
    )
    (comp (ref "U2")
      (value "AT25DFXX1X-M")
      (footprint "eagle-import:8MA1-UDFN")
      (libsource (lib "eagle-import") (part "AT25DFXX1X-M"))
    )
    (comp (ref "VREF")
      (value "TPSQTP13SQ")
      (footprint "eagle-import:TP13SQ")
      (libsource (lib "eagle-import") (part "TPSQTP13SQ"))
    )
  )
  (nets
    (net (code "1") (name "+3V3") (class "Default")
      (node (ref "3.3_V_REG") (pin "P$2") (pinfunction "VOUT_P$2") (pintype "bidirectional"))
      (node (ref "3.3_V_REG") (pin "P$3") (pinfunction "VOUT_P$3") (pintype "bidirectional"))
      (node (ref "3.3_V_REG") (pin "P$6") (pinfunction "VOUT_P$6") (pintype "bidirectional"))
      (node (ref "3.3_V_REG") (pin "P$7") (pinfunction "VOUT_P$7") (pintype "bidirectional"))
      (node (ref "C10") (pin "1") (pinfunction "1_1") (pintype "passive"))
      (node (ref "C13") (pin "1") (pinfunction "1_1") (pintype "passive"))
      (node (ref "C16") (pin "POS") (pinfunction "POS_POS") (pintype "bidirectional"))
      (node (ref "C19") (pin "1") (pinfunction "1_1") (pintype "passive"))
      (node (ref "C21") (pin "2") (pinfunction "2_2") (pintype "passive"))
      (node (ref "C22") (pin "2") (pinfunction "2_2") (pintype "passive"))
      (node (ref "C23") (pin "2") (pinfunction "2_2") (pintype "passive"))
      (node (ref "C24") (pin "2") (pinfunction "2_2") (pintype "passive"))
      (node (ref "C26") (pin "1") (pinfunction "1_1") (pintype "passive"))
      (node (ref "C27") (pin "1") (pinfunction "1_1") (pintype "passive"))
      (node (ref "C28") (pin "1") (pinfunction "1_1") (pintype "passive"))
      (node (ref "C29") (pin "1") (pinfunction "1_1") (pintype "passive"))
      (node (ref "C30") (pin "1") (pinfunction "1_1") (pintype "passive"))
      (node (ref "C31") (pin "1") (pinfunction "1_1") (pintype "passive"))
      (node (ref "C32") (pin "1") (pinfunction "1_1") (pintype "passive"))
      (node (ref "C33") (pin "1") (pinfunction "1_1") (pintype "passive"))
      (node (ref "C34") (pin "1") (pinfunction "1_1") (pintype "passive"))
      (node (ref "C35") (pin "1") (pinfunction "1_1") (pintype "passive"))
      (node (ref "C36") (pin "POS") (pinfunction "POS_POS") (pintype "bidirectional"))
      (node (ref "C4") (pin "1") (pinfunction "1_1") (pintype "passive"))
      (node (ref "C5") (pin "1") (pinfunction "1_1") (pintype "passive"))
      (node (ref "C9") (pin "1") (pinfunction "1_1") (pintype "passive"))
      (node (ref "J1") (pin "P$1") (pinfunction "VCC_P$1") (pintype "bidirectional"))
      (node (ref "J4") (pin "1") (pinfunction "1_1") (pintype "passive"))
      (node (ref "JP1") (pin "3") (pinfunction "3_3") (pintype "passive"))
      (node (ref "R17") (pin "1") (pinfunction "1_1") (pintype "passive"))
      (node (ref "R2") (pin "2") (pinfunction "2_2") (pintype "passive"))
      (node (ref "R24") (pin "2") (pinfunction "2_2") (pintype "passive"))
      (node (ref "R30") (pin "2") (pinfunction "2_2") (pintype "passive"))
      (node (ref "R4") (pin "2") (pinfunction "2_2") (pintype "passive"))
      (node (ref "R40") (pin "2") (pinfunction "2_2") (pintype "passive"))
      (node (ref "R41") (pin "2") (pinfunction "2_2") (pintype "passive"))
      (node (ref "R42") (pin "2") (pinfunction "2_2") (pintype "passive"))
      (node (ref "R43") (pin "2") (pinfunction "2_2") (pintype "passive"))
      (node (ref "R5") (pin "2") (pinfunction "2_2") (pintype "passive"))
      (node (ref "R6") (pin "1") (pinfunction "1_1") (pintype "passive"))
      (node (ref "SW1") (pin "P$1") (pinfunction "P$1_P$1") (pintype "bidirectional"))
      (node (ref "SW1") (pin "P$2") (pinfunction "P$2_P$2") (pintype "bidirectional"))
      (node (ref "SW2") (pin "P$1") (pinfunction "P$1_P$1") (pintype "bidirectional"))
      (node (ref "SW2") (pin "P$2") (pinfunction "P$2_P$2") (pintype "bidirectional"))
      (node (ref "SW3") (pin "P$1") (pinfunction "P$1_P$1") (pintype "bidirectional"))
      (node (ref "SW3") (pin "P$2") (pinfunction "P$2_P$2") (pintype "bidirectional"))
      (node (ref "SW4") (pin "P$1") (pinfunction "P$1_P$1") (pintype "bidirectional"))
      (node (ref "SW4") (pin "P$2") (pinfunction "P$2_P$2") (pintype "bidirectional"))
      (node (ref "SW5") (pin "P$1") (pinfunction "P$1_P$1") (pintype "bidirectional"))
      (node (ref "SW5") (pin "P$2") (pinfunction "P$2_P$2") (pintype "bidirectional"))
      (node (ref "SW6") (pin "P$1") (pinfunction "P$1_P$1") (pintype "bidirectional"))
      (node (ref "SW6") (pin "P$2") (pinfunction "P$2_P$2") (pintype "bidirectional"))
      (node (ref "TP_+3V30") (pin "TP") (pinfunction "TP_TP") (pintype "input"))
      (node (ref "TP_+3V31") (pin "TP") (pinfunction "TP_TP") (pintype "input"))
      (node (ref "TP_+3V32") (pin "TP") (pinfunction "TP_TP") (pintype "input"))
      (node (ref "TP_+3V33") (pin "TP") (pinfunction "TP_TP") (pintype "input"))
      (node (ref "U$1") (pin "P$100") (pinfunction "VCC_P$100") (pintype "bidirectional"))
      (node (ref "U$1") (pin "P$23") (pinfunction "VCCIO3_P$23") (pintype "bidirectional"))
      (node (ref "U$1") (pin "P$26") (pinfunction "VCCIO2_P$26") (pintype "bidirectional"))
      (node (ref "U$1") (pin "P$46") (pinfunction "VCCIO2_P$46") (pintype "bidirectional"))
      (node (ref "U$1") (pin "P$5") (pinfunction "VCCIO3_P$5") (pintype "bidirectional"))
      (node (ref "U$1") (pin "P$50") (pinfunction "VCC_P$50") (pintype "bidirectional"))
      (node (ref "U$1") (pin "P$55") (pinfunction "VCCIO1_P$55") (pintype "bidirectional"))
      (node (ref "U$1") (pin "P$73") (pinfunction "VCCIO1_P$73") (pintype "bidirectional"))
      (node (ref "U$1") (pin "P$80") (pinfunction "VCCIO0_P$80") (pintype "bidirectional"))
      (node (ref "U$1") (pin "P$93") (pinfunction "VCCIO0_P$93") (pintype "bidirectional"))
      (node (ref "U$11") (pin "D") (pinfunction "D_D") (pintype "bidirectional"))
      (node (ref "U$2") (pin "13") (pinfunction "VPA_13") (pintype "bidirectional"))
      (node (ref "U$2") (pin "18") (pinfunction "VCC_18") (pintype "bidirectional"))
      (node (ref "U$2") (pin "6") (pinfunction "VIO_6") (pintype "bidirectional"))
      (node (ref "U$2") (pin "7") (pinfunction "VDD_7") (pintype "bidirectional"))
      (node (ref "U$4") (pin "P$38") (pinfunction "P$38_P$38") (pintype "bidirectional"))
      (node (ref "U$4") (pin "P$7") (pinfunction "P$7_P$7") (pintype "bidirectional"))
      (node (ref "U$4") (pin "P$8") (pinfunction "P$8_P$8") (pintype "bidirectional"))
      (node (ref "U$7") (pin "P$6") (pinfunction "VDD_P$6") (pintype "bidirectional"))
      (node (ref "U$9") (pin "P$6") (pinfunction "VDD_P$6") (pintype "bidirectional"))
      (node (ref "U1") (pin "P$18") (pinfunction "VDDIO_P$18") (pintype "bidirectional"))
      (node (ref "U1") (pin "P$45") (pinfunction "VDDIO_P$45") (pintype "bidirectional"))
      (node (ref "U1") (pin "P$58") (pinfunction "VDDIO_P$58") (pintype "bidirectional"))
      (node (ref "U1") (pin "P$7") (pinfunction "VDDIN_P$7") (pintype "bidirectional"))
      (node (ref "U2") (pin "P$3") (pinfunction "~{WP}_P$3") (pintype "input"))
      (node (ref "U2") (pin "P$7") (pinfunction "~{HOLD}_P$7") (pintype "input"))
      (node (ref "U2") (pin "P$8") (pinfunction "VCC_P$8") (pintype "power_in"))
    )
    (net (code "2") (name "+5V0") (class "Default")
      (node (ref "5.0_V_REG") (pin "P$2") (pinfunction "VOUT_P$2") (pintype "bidirectional"))
      (node (ref "5.0_V_REG") (pin "P$3") (pinfunction "VOUT_P$3") (pintype "bidirectional"))
      (node (ref "5.0_V_REG") (pin "P$6") (pinfunction "VOUT_P$6") (pintype "bidirectional"))
      (node (ref "5.0_V_REG") (pin "P$7") (pinfunction "VOUT_P$7") (pintype "bidirectional"))
      (node (ref "C15") (pin "POS") (pinfunction "POS_POS") (pintype "bidirectional"))
      (node (ref "C37") (pin "POS") (pinfunction "POS_POS") (pintype "bidirectional"))
      (node (ref "C38") (pin "1") (pinfunction "1_1") (pintype "passive"))
      (node (ref "C42") (pin "1") (pinfunction "1_1") (pintype "passive"))
      (node (ref "JP1") (pin "1") (pinfunction "1_1") (pintype "passive"))
      (node (ref "TP_+5V0") (pin "TP") (pinfunction "TP_TP") (pintype "input"))
      (node (ref "U$9") (pin "P$16") (pinfunction "VCC2_P$16") (pintype "bidirectional"))
      (node (ref "U$9") (pin "P$8") (pinfunction "VCC1_P$8") (pintype "bidirectional"))
    )
    (net (code "3") (name "/~{DISP_READ}") (class "Default")
      (node (ref "U$1") (pin "P$53") (pinfunction "PR7B_P$53") (pintype "bidirectional"))
      (node (ref "U$4") (pin "P$13") (pinfunction "P$13_P$13") (pintype "bidirectional"))
    )
    (net (code "4") (name "/~{DISP_RESET}") (class "Default")
      (node (ref "R40") (pin "1") (pinfunction "1_1") (pintype "passive"))
      (node (ref "U$4") (pin "P$30") (pinfunction "P$30_P$30") (pintype "bidirectional"))
      (node (ref "U1") (pin "P$31") (pinfunction "PA8/XOUT32/PGMM0_P$31") (pintype "bidirectional"))
    )
    (net (code "5") (name "/~{DISP_WRITE}") (class "Default")
      (node (ref "U$1") (pin "P$52") (pinfunction "PR7C_P$52") (pintype "bidirectional"))
      (node (ref "U$4") (pin "P$12") (pinfunction "P$12_P$12") (pintype "bidirectional"))
    )
    (net (code "6") (name "CPLD_JTAG_TCK") (class "Default")
      (node (ref "J4") (pin "9") (pinfunction "9_9") (pintype "passive"))
      (node (ref "U$1") (pin "P$91") (pinfunction "PT7C/TCK_P$91") (pintype "bidirectional"))
    )
    (net (code "7") (name "CPLD_JTAG_TDI") (class "Default")
      (node (ref "J4") (pin "5") (pinfunction "5_5") (pintype "passive"))
      (node (ref "U$1") (pin "P$94") (pinfunction "PT7B/TDI_P$94") (pintype "bidirectional"))
    )
    (net (code "8") (name "CPLD_JTAG_TDO") (class "Default")
      (node (ref "J4") (pin "13") (pinfunction "13_13") (pintype "passive"))
      (node (ref "U$1") (pin "P$95") (pinfunction "PT7A/TDO_P$95") (pintype "bidirectional"))
    )
    (net (code "9") (name "CPLD_JTAG_TMS") (class "Default")
      (node (ref "J4") (pin "7") (pinfunction "7_7") (pintype "passive"))
      (node (ref "U$1") (pin "P$90") (pinfunction "PT7D/TMS_P$90") (pintype "bidirectional"))
    )
    (net (code "10") (name "CPLD_PROGRAMN") (class "Default")
      (node (ref "R41") (pin "1") (pinfunction "1_1") (pintype "passive"))
      (node (ref "SB5") (pin "P$1") (pinfunction "P$1_P$1") (pintype "bidirectional"))
      (node (ref "SW8") (pin "P$1") (pinfunction "P$1_P$1") (pintype "bidirectional"))
      (node (ref "SW8") (pin "P$2") (pinfunction "P$2_P$2") (pintype "bidirectional"))
      (node (ref "U$1") (pin "P$81") (pinfunction "PT10D/PROGRAMN_P$81") (pintype "bidirectional"))
    )
    (net (code "11") (name "CPLD_SYS_CLK") (class "Default")
      (node (ref "C25") (pin "1") (pinfunction "1_1") (pintype "passive"))
      (node (ref "R12") (pin "2") (pinfunction "2_2") (pintype "passive"))
      (node (ref "U$1") (pin "P$38") (pinfunction "PB10C/PCLKT2_1_P$38") (pintype "bidirectional"))
    )
    (net (code "12") (name "D+") (class "Default")
      (node (ref "R13") (pin "1") (pinfunction "1_1") (pintype "passive"))
      (node (ref "U1") (pin "P$57") (pinfunction "DDP/PB11_P$57") (pintype "bidirectional"))
    )
    (net (code "13") (name "D-") (class "Default")
      (node (ref "R14") (pin "1") (pinfunction "1_1") (pintype "passive"))
      (node (ref "U1") (pin "P$56") (pinfunction "DDM/PB10_P$56") (pintype "bidirectional"))
    )
    (net (code "14") (name "DISP_CHIP_SELECT") (class "Default")
      (node (ref "U$1") (pin "P$96") (pinfunction "PT6D_P$96") (pintype "bidirectional"))
      (node (ref "U$4") (pin "P$10") (pinfunction "P$10_P$10") (pintype "bidirectional"))
    )
    (net (code "15") (name "DISP_DATA_COMMAND") (class "Default")
      (node (ref "U$1") (pin "P$51") (pinfunction "PR7D_P$51") (pintype "bidirectional"))
      (node (ref "U$4") (pin "P$11") (pinfunction "P$11_P$11") (pintype "bidirectional"))
    )
    (net (code "16") (name "DISP_DB0") (class "Default")
      (node (ref "U$1") (pin "P$54") (pinfunction "PR7A_P$54") (pintype "bidirectional"))
      (node (ref "U$4") (pin "P$14") (pinfunction "P$14_P$14") (pintype "bidirectional"))
    )
    (net (code "17") (name "DISP_DB1") (class "Default")
      (node (ref "U$1") (pin "P$57") (pinfunction "PR6D_P$57") (pintype "bidirectional"))
      (node (ref "U$4") (pin "P$15") (pinfunction "P$15_P$15") (pintype "bidirectional"))
    )
    (net (code "18") (name "DISP_DB2") (class "Default")
      (node (ref "U$1") (pin "P$58") (pinfunction "PR6C_P$58") (pintype "bidirectional"))
      (node (ref "U$4") (pin "P$16") (pinfunction "P$16_P$16") (pintype "bidirectional"))
    )
    (net (code "19") (name "DISP_DB3") (class "Default")
      (node (ref "U$1") (pin "P$59") (pinfunction "PR6B_P$59") (pintype "bidirectional"))
      (node (ref "U$4") (pin "P$17") (pinfunction "P$17_P$17") (pintype "bidirectional"))
    )
    (net (code "20") (name "DISP_DB4") (class "Default")
      (node (ref "U$1") (pin "P$60") (pinfunction "PR6A_P$60") (pintype "bidirectional"))
      (node (ref "U$4") (pin "P$18") (pinfunction "P$18_P$18") (pintype "bidirectional"))
    )
    (net (code "21") (name "DISP_DB5") (class "Default")
      (node (ref "U$1") (pin "P$64") (pinfunction "PR5B_P$64") (pintype "bidirectional"))
      (node (ref "U$4") (pin "P$19") (pinfunction "P$19_P$19") (pintype "bidirectional"))
    )
    (net (code "22") (name "DISP_DB6") (class "Default")
      (node (ref "U$1") (pin "P$65") (pinfunction "PR5A_P$65") (pintype "bidirectional"))
      (node (ref "U$4") (pin "P$20") (pinfunction "P$20_P$20") (pintype "bidirectional"))
    )
    (net (code "23") (name "DISP_DB7") (class "Default")
      (node (ref "U$1") (pin "P$66") (pinfunction "PR3D_P$66") (pintype "bidirectional"))
      (node (ref "U$4") (pin "P$21") (pinfunction "P$21_P$21") (pintype "bidirectional"))
    )
    (net (code "24") (name "DISP_DB8") (class "Default")
      (node (ref "U$1") (pin "P$67") (pinfunction "PR3C_P$67") (pintype "bidirectional"))
      (node (ref "U$4") (pin "P$22") (pinfunction "P$22_P$22") (pintype "bidirectional"))
    )
    (net (code "25") (name "DISP_DB9") (class "Default")
      (node (ref "U$1") (pin "P$68") (pinfunction "PR3B_P$68") (pintype "bidirectional"))
      (node (ref "U$4") (pin "P$23") (pinfunction "P$23_P$23") (pintype "bidirectional"))
    )
    (net (code "26") (name "DISP_DB10") (class "Default")
      (node (ref "U$1") (pin "P$69") (pinfunction "PR3A_P$69") (pintype "bidirectional"))
      (node (ref "U$4") (pin "P$24") (pinfunction "P$24_P$24") (pintype "bidirectional"))
    )
    (net (code "27") (name "DISP_DB11") (class "Default")
      (node (ref "U$1") (pin "P$70") (pinfunction "PR2D_P$70") (pintype "bidirectional"))
      (node (ref "U$4") (pin "P$25") (pinfunction "P$25_P$25") (pintype "bidirectional"))
    )
    (net (code "28") (name "DISP_DB12") (class "Default")
      (node (ref "U$1") (pin "P$71") (pinfunction "PR2C_P$71") (pintype "bidirectional"))
      (node (ref "U$4") (pin "P$26") (pinfunction "P$26_P$26") (pintype "bidirectional"))
    )
    (net (code "29") (name "DISP_DB13") (class "Default")
      (node (ref "U$1") (pin "P$74") (pinfunction "PR2B_P$74") (pintype "bidirectional"))
      (node (ref "U$4") (pin "P$27") (pinfunction "P$27_P$27") (pintype "bidirectional"))
    )
    (net (code "30") (name "DISP_DB14") (class "Default")
      (node (ref "U$1") (pin "P$75") (pinfunction "PR2A_P$75") (pintype "bidirectional"))
      (node (ref "U$4") (pin "P$28") (pinfunction "P$28_P$28") (pintype "bidirectional"))
    )
    (net (code "31") (name "DISP_DB15") (class "Default")
      (node (ref "U$1") (pin "P$78") (pinfunction "PT11A_P$78") (pintype "bidirectional"))
      (node (ref "U$4") (pin "P$29") (pinfunction "P$29_P$29") (pintype "bidirectional"))
    )
    (net (code "32") (name "DISP_FMARK") (class "Default")
      (node (ref "U$1") (pin "P$84") (pinfunction "PT10A_P$84") (pintype "bidirectional"))
      (node (ref "U$4") (pin "P$9") (pinfunction "P$9_P$9") (pintype "bidirectional"))
    )
    (net (code "33") (name "DISP_ID") (class "Default")
      (node (ref "U$1") (pin "P$83") (pinfunction "PT10B_P$83") (pintype "bidirectional"))
      (node (ref "U$4") (pin "P$6") (pinfunction "P$6_P$6") (pintype "bidirectional"))
    )
    (net (code "34") (name "DISP_SPI_CS") (class "Default")
      (node (ref "SB4") (pin "P$1") (pinfunction "P$1_P$1") (pintype "bidirectional"))
      (node (ref "U$1") (pin "P$48") (pinfunction "PB14C/SN_P$48") (pintype "bidirectional"))
      (node (ref "U1") (pin "P$28") (pinfunction "PA11/PGMM3_P$28") (pintype "bidirectional"))
    )
    (net (code "35") (name "DISP_SPI_MISO") (class "Default")
      (node (ref "SB1") (pin "P$1") (pinfunction "P$1_P$1") (pintype "bidirectional"))
      (node (ref "U$1") (pin "P$32") (pinfunction "PB6B/SO/SPISO_P$32") (pintype "bidirectional"))
      (node (ref "U1") (pin "P$27") (pinfunction "PA12/PGMD0_P$27") (pintype "bidirectional"))
    )
    (net (code "36") (name "DISP_SPI_MOSI") (class "Default")
      (node (ref "SB3") (pin "P$1") (pinfunction "P$1_P$1") (pintype "bidirectional"))
      (node (ref "U$1") (pin "P$49") (pinfunction "PB14D/SI/SISPI_P$49") (pintype "bidirectional"))
      (node (ref "U1") (pin "P$22") (pinfunction "PA13/PGMD1_P$22") (pintype "bidirectional"))
    )
    (net (code "37") (name "DISP_SPI_SPCK") (class "Default")
      (node (ref "SB2") (pin "P$1") (pinfunction "P$1_P$1") (pintype "bidirectional"))
      (node (ref "U$1") (pin "P$31") (pinfunction "PB6A/MCLK/CCLK_P$31") (pintype "bidirectional"))
      (node (ref "U1") (pin "P$21") (pinfunction "PA14/PGMD2_P$21") (pintype "bidirectional"))
    )
    (net (code "38") (name "ENC_A") (class "Default")
      (node (ref "R42") (pin "1") (pinfunction "1_1") (pintype "passive"))
      (node (ref "U$1") (pin "P$1") (pinfunction "PL2A_P$1") (pintype "bidirectional"))
      (node (ref "U$11") (pin "A") (pinfunction "A_A") (pintype "bidirectional"))
    )
    (net (code "39") (name "ENC_B") (class "Default")
      (node (ref "R43") (pin "1") (pinfunction "1_1") (pintype "passive"))
      (node (ref "U$1") (pin "P$2") (pinfunction "PL2B_P$2") (pintype "bidirectional"))
      (node (ref "U$11") (pin "B") (pinfunction "B_B") (pintype "bidirectional"))
    )
    (net (code "40") (name "ENC_SWITCH") (class "Default")
      (node (ref "R44") (pin "2") (pinfunction "2_2") (pintype "passive"))
      (node (ref "U$1") (pin "P$24") (pinfunction "PL7C_P$24") (pintype "bidirectional"))
      (node (ref "U$11") (pin "E") (pinfunction "E_E") (pintype "bidirectional"))
    )
    (net (code "41") (name "FLASH_CS") (class "Default")
      (node (ref "U1") (pin "P$32") (pinfunction "PA7/XIN32/PGMNVALID_P$32") (pintype "bidirectional"))
      (node (ref "U2") (pin "P$1") (pinfunction "~{CS}_P$1") (pintype "input"))
    )
    (net (code "42") (name "FLASH_MISO") (class "Default")
      (node (ref "U1") (pin "P$35") (pinfunction "PA5/PGMRDY_P$35") (pintype "bidirectional"))
      (node (ref "U2") (pin "P$2") (pinfunction "SO(SOI)_P$2") (pintype "bidirectional"))
    )
    (net (code "43") (name "FLASH_MOSI") (class "Default")
      (node (ref "U1") (pin "P$34") (pinfunction "PA6/PGMNOE_P$34") (pintype "bidirectional"))
      (node (ref "U2") (pin "P$5") (pinfunction "SI(SIO)_P$5") (pintype "bidirectional"))
    )
    (net (code "44") (name "FLASH_SPCK") (class "Default")
      (node (ref "U1") (pin "P$44") (pinfunction "PA2/PGMEN2_P$44") (pintype "bidirectional"))
      (node (ref "U2") (pin "P$6") (pinfunction "SCK_P$6") (pintype "bidirectional"))
    )
    (net (code "45") (name "GND") (class "Default")
      (node (ref "3.3_V_REG") (pin "P$1") (pinfunction "GND/ADJ_P$1") (pintype "bidirectional"))
      (node (ref "5.0_V_REG") (pin "P$1") (pinfunction "GND/ADJ_P$1") (pintype "bidirectional"))
      (node (ref "C1") (pin "2") (pinfunction "2_2") (pintype "passive"))
      (node (ref "C10") (pin "2") (pinfunction "2_2") (pintype "passive"))
      (node (ref "C11") (pin "2") (pinfunction "2_2") (pintype "passive"))
      (node (ref "C12") (pin "2") (pinfunction "2_2") (pintype "passive"))
      (node (ref "C13") (pin "2") (pinfunction "2_2") (pintype "passive"))
      (node (ref "C14") (pin "2") (pinfunction "2_2") (pintype "passive"))
      (node (ref "C15") (pin "NEG") (pinfunction "NEG_NEG") (pintype "bidirectional"))
      (node (ref "C16") (pin "NEG") (pinfunction "NEG_NEG") (pintype "bidirectional"))
      (node (ref "C17") (pin "2") (pinfunction "2_2") (pintype "passive"))
      (node (ref "C18") (pin "2") (pinfunction "2_2") (pintype "passive"))
      (node (ref "C19") (pin "2") (pinfunction "2_2") (pintype "passive"))
      (node (ref "C2") (pin "2") (pinfunction "2_2") (pintype "passive"))
      (node (ref "C20") (pin "2") (pinfunction "2_2") (pintype "passive"))
      (node (ref "C21") (pin "1") (pinfunction "1_1") (pintype "passive"))
      (node (ref "C22") (pin "1") (pinfunction "1_1") (pintype "passive"))
      (node (ref "C23") (pin "1") (pinfunction "1_1") (pintype "passive"))
      (node (ref "C24") (pin "1") (pinfunction "1_1") (pintype "passive"))
      (node (ref "C25") (pin "2") (pinfunction "2_2") (pintype "passive"))
      (node (ref "C26") (pin "2") (pinfunction "2_2") (pintype "passive"))
      (node (ref "C27") (pin "2") (pinfunction "2_2") (pintype "passive"))
      (node (ref "C28") (pin "2") (pinfunction "2_2") (pintype "passive"))
      (node (ref "C29") (pin "2") (pinfunction "2_2") (pintype "passive"))
      (node (ref "C3") (pin "2") (pinfunction "2_2") (pintype "passive"))
      (node (ref "C30") (pin "2") (pinfunction "2_2") (pintype "passive"))
      (node (ref "C31") (pin "2") (pinfunction "2_2") (pintype "passive"))
      (node (ref "C32") (pin "2") (pinfunction "2_2") (pintype "passive"))
      (node (ref "C33") (pin "2") (pinfunction "2_2") (pintype "passive"))
      (node (ref "C34") (pin "2") (pinfunction "2_2") (pintype "passive"))
      (node (ref "C35") (pin "2") (pinfunction "2_2") (pintype "passive"))
      (node (ref "C36") (pin "NEG") (pinfunction "NEG_NEG") (pintype "bidirectional"))
      (node (ref "C37") (pin "NEG") (pinfunction "NEG_NEG") (pintype "bidirectional"))
      (node (ref "C38") (pin "2") (pinfunction "2_2") (pintype "passive"))
      (node (ref "C39") (pin "NEG") (pinfunction "NEG_NEG") (pintype "bidirectional"))
      (node (ref "C4") (pin "2") (pinfunction "2_2") (pintype "passive"))
      (node (ref "C42") (pin "2") (pinfunction "2_2") (pintype "passive"))
      (node (ref "C43") (pin "NEG") (pinfunction "NEG_NEG") (pintype "bidirectional"))
      (node (ref "C5") (pin "2") (pinfunction "2_2") (pintype "passive"))
      (node (ref "C6") (pin "2") (pinfunction "2_2") (pintype "passive"))
      (node (ref "C7") (pin "2") (pinfunction "2_2") (pintype "passive"))
      (node (ref "C8") (pin "2") (pinfunction "2_2") (pintype "passive"))
      (node (ref "C9") (pin "2") (pinfunction "2_2") (pintype "passive"))
      (node (ref "D1") (pin "CATH") (pinfunction "CATH_CATH") (pintype "bidirectional"))
      (node (ref "D2") (pin "CATH") (pinfunction "CATH_CATH") (pintype "bidirectional"))
      (node (ref "D3") (pin "CATH") (pinfunction "CATH_CATH") (pintype "bidirectional"))
      (node (ref "D4") (pin "CATH") (pinfunction "CATH_CATH") (pintype "bidirectional"))
      (node (ref "J1") (pin "P$3") (pinfunction "GND_P$3") (pintype "bidirectional"))
      (node (ref "J1") (pin "P$5") (pinfunction "GND_P$5") (pintype "bidirectional"))
      (node (ref "J2") (pin "GND") (pinfunction "GND_GND") (pintype "bidirectional"))
      (node (ref "J3") (pin "P$5") (pinfunction "GND_P$5") (pintype "bidirectional"))
      (node (ref "J4") (pin "10") (pinfunction "10_10") (pintype "passive"))
      (node (ref "J4") (pin "11") (pinfunction "11_11") (pintype "passive"))
      (node (ref "J4") (pin "12") (pinfunction "12_12") (pintype "passive"))
      (node (ref "J4") (pin "14") (pinfunction "14_14") (pintype "passive"))
      (node (ref "J4") (pin "16") (pinfunction "16_16") (pintype "passive"))
      (node (ref "J4") (pin "18") (pinfunction "18_18") (pintype "passive"))
      (node (ref "J4") (pin "20") (pinfunction "20_20") (pintype "passive"))
      (node (ref "J4") (pin "4") (pinfunction "4_4") (pintype "passive"))
      (node (ref "J4") (pin "6") (pinfunction "6_6") (pintype "passive"))
      (node (ref "J4") (pin "8") (pinfunction "8_8") (pintype "passive"))
      (node (ref "J5") (pin "P$5") (pinfunction "GND_P$5") (pintype "bidirectional"))
      (node (ref "R1") (pin "2") (pinfunction "2_2") (pintype "passive"))
      (node (ref "R16") (pin "1") (pinfunction "1_1") (pintype "passive"))
      (node (ref "R18") (pin "1") (pinfunction "1_1") (pintype "passive"))
      (node (ref "R20") (pin "2") (pinfunction "2_2") (pintype "passive"))
      (node (ref "R31") (pin "2") (pinfunction "2_2") (pintype "passive"))
      (node (ref "R32") (pin "2") (pinfunction "2_2") (pintype "passive"))
      (node (ref "R33") (pin "2") (pinfunction "2_2") (pintype "passive"))
      (node (ref "R34") (pin "1") (pinfunction "1_1") (pintype "passive"))
      (node (ref "R35") (pin "1") (pinfunction "1_1") (pintype "passive"))
      (node (ref "R36") (pin "1") (pinfunction "1_1") (pintype "passive"))
      (node (ref "R37") (pin "1") (pinfunction "1_1") (pintype "passive"))
      (node (ref "R38") (pin "1") (pinfunction "1_1") (pintype "passive"))
      (node (ref "R39") (pin "1") (pinfunction "1_1") (pintype "passive"))
      (node (ref "R44") (pin "1") (pinfunction "1_1") (pintype "passive"))
      (node (ref "R7") (pin "1") (pinfunction "1_1") (pintype "passive"))
      (node (ref "SW7") (pin "P$1") (pinfunction "P$1_P$1") (pintype "bidirectional"))
      (node (ref "SW7") (pin "P$2") (pinfunction "P$2_P$2") (pintype "bidirectional"))
      (node (ref "SW8") (pin "P$3") (pinfunction "P$3_P$3") (pintype "bidirectional"))
      (node (ref "SW8") (pin "P$4") (pinfunction "P$4_P$4") (pintype "bidirectional"))
      (node (ref "TP_GND0") (pin "TP") (pinfunction "TP_TP") (pintype "input"))
      (node (ref "TP_GND1") (pin "TP") (pinfunction "TP_TP") (pintype "input"))
      (node (ref "TP_GND2") (pin "TP") (pinfunction "TP_TP") (pintype "input"))
      (node (ref "TP_GND3") (pin "TP") (pinfunction "TP_TP") (pintype "input"))
      (node (ref "U$1") (pin "P$22") (pinfunction "GND_P$22") (pintype "bidirectional"))
      (node (ref "U$1") (pin "P$33") (pinfunction "GND_P$33") (pintype "bidirectional"))
      (node (ref "U$1") (pin "P$44") (pinfunction "GND_P$44") (pintype "bidirectional"))
      (node (ref "U$1") (pin "P$56") (pinfunction "GND_P$56") (pintype "bidirectional"))
      (node (ref "U$1") (pin "P$6") (pinfunction "GND_P$6") (pintype "bidirectional"))
      (node (ref "U$1") (pin "P$72") (pinfunction "GND_P$72") (pintype "bidirectional"))
      (node (ref "U$1") (pin "P$79") (pinfunction "GND_P$79") (pintype "bidirectional"))
      (node (ref "U$1") (pin "P$92") (pinfunction "GND_P$92") (pintype "bidirectional"))
      (node (ref "U$10") (pin "P$17") (pinfunction "GND_PAD_P$17") (pintype "bidirectional"))
      (node (ref "U$10") (pin "P$2") (pinfunction "GND_P$2") (pintype "bidirectional"))
      (node (ref "U$10") (pin "P$6") (pinfunction "PGND_P$6") (pintype "bidirectional"))
      (node (ref "U$11") (pin "C") (pinfunction "COM_C") (pintype "bidirectional"))
      (node (ref "U$2") (pin "12") (pinfunction "PGND_12") (pintype "bidirectional"))
      (node (ref "U$2") (pin "17") (pinfunction "AGND_17") (pintype "bidirectional"))
      (node (ref "U$2") (pin "8") (pinfunction "DGND_8") (pintype "bidirectional"))
      (node (ref "U$3") (pin "P$2") (pinfunction "GND_P$2") (pintype "bidirectional"))
      (node (ref "U$3") (pin "P$4") (pinfunction "GND_P$4") (pintype "bidirectional"))
      (node (ref "U$4") (pin "P$1") (pinfunction "P$1_P$1") (pintype "bidirectional"))
      (node (ref "U$4") (pin "P$39") (pinfunction "P$39_P$39") (pintype "bidirectional"))
      (node (ref "U$7") (pin "GND_PAD") (pinfunction "GND_PAD_GND_PAD") (pintype "bidirectional"))
      (node (ref "U$7") (pin "P$3") (pinfunction "GND_P$3") (pintype "bidirectional"))
      (node (ref "U$9") (pin "P$10") (pinfunction "AGND1_P$10") (pintype "bidirectional"))
      (node (ref "U$9") (pin "P$15") (pinfunction "AGND2_P$15") (pintype "bidirectional"))
      (node (ref "U$9") (pin "P$7") (pinfunction "DGND_P$7") (pintype "bidirectional"))
      (node (ref "U1") (pin "P$17") (pinfunction "GND_P$17") (pintype "bidirectional"))
      (node (ref "U1") (pin "P$2") (pinfunction "GND_P$2") (pintype "bidirectional"))
      (node (ref "U1") (pin "P$46") (pinfunction "GND_P$46") (pintype "bidirectional"))
      (node (ref "U1") (pin "P$60") (pinfunction "GND_P$60") (pintype "bidirectional"))
      (node (ref "U2") (pin "P$4") (pinfunction "GND_P$4") (pintype "power_in"))
      (node (ref "U2") (pin "P$9") (pinfunction "PAD_P$9") (pintype "power_in"))
    )
    (net (code "46") (name "I2S_BCK") (class "Default")
      (node (ref "R22") (pin "1") (pinfunction "1_1") (pintype "passive"))
      (node (ref "U$2") (pin "10") (pinfunction "BCK_10") (pintype "bidirectional"))
      (node (ref "U$9") (pin "P$2") (pinfunction "BCK_P$2") (pintype "bidirectional"))
    )
    (net (code "47") (name "I2S_DATA") (class "Default")
      (node (ref "R21") (pin "1") (pinfunction "1_1") (pintype "passive"))
      (node (ref "U$2") (pin "5") (pinfunction "DIN_5") (pintype "bidirectional"))
      (node (ref "U$9") (pin "P$3") (pinfunction "DIN_P$3") (pintype "bidirectional"))
    )
    (net (code "48") (name "I2S_LRCK") (class "Default")
      (node (ref "R23") (pin "1") (pinfunction "1_1") (pintype "passive"))
      (node (ref "U$2") (pin "11") (pinfunction "LRCK_11") (pintype "bidirectional"))
      (node (ref "U$9") (pin "P$1") (pinfunction "LRCK_P$1") (pintype "bidirectional"))
    )
    (net (code "49") (name "LCD_BACKLIGHT_PWM") (class "Default")
      (node (ref "R19") (pin "2") (pinfunction "2_2") (pintype "passive"))
      (node (ref "R20") (pin "1") (pinfunction "1_1") (pintype "passive"))
      (node (ref "U1") (pin "P$3") (pinfunction "PB0/AD4_P$3") (pintype "bidirectional"))
    )
    (net (code "50") (name "LED_1") (class "Default")
      (node (ref "R45") (pin "1") (pinfunction "1_1") (pintype "passive"))
      (node (ref "U1") (pin "P$6") (pinfunction "PB3/AD7_P$6") (pintype "bidirectional"))
    )
    (net (code "51") (name "LED_2") (class "Default")
      (node (ref "R46") (pin "1") (pinfunction "1_1") (pintype "passive"))
      (node (ref "U1") (pin "P$5") (pinfunction "PB2/AD6_P$5") (pintype "bidirectional"))
    )
    (net (code "52") (name "LED_3") (class "Default")
      (node (ref "R47") (pin "1") (pinfunction "1_1") (pintype "passive"))
      (node (ref "U1") (pin "P$4") (pinfunction "PB1/AD5_P$4") (pintype "bidirectional"))
    )
    (net (code "53") (name "MAX98307_PUMP_VSS") (class "Default")
      (node (ref "C43") (pin "POS") (pinfunction "POS_POS") (pintype "bidirectional"))
      (node (ref "U$10") (pin "P$14") (pinfunction "PVSS_P$14") (pintype "bidirectional"))
      (node (ref "U$10") (pin "P$7") (pinfunction "SVSS_P$7") (pintype "bidirectional"))
    )
    (net (code "54") (name "MAX98307_VCC") (class "Default")
      (node (ref "JP1") (pin "2") (pinfunction "2_2") (pintype "passive"))
      (node (ref "U$10") (pin "P$1") (pinfunction "~{SHDN}_P$1") (pintype "bidirectional"))
      (node (ref "U$10") (pin "P$13") (pinfunction "VCC_P$13") (pintype "bidirectional"))
      (node (ref "U$10") (pin "P$3") (pinfunction "PVDD_P$3") (pintype "bidirectional"))
    )
    (net (code "55") (name "N$38") (class "Default")
      (node (ref "C39") (pin "POS") (pinfunction "POS_POS") (pintype "bidirectional"))
      (node (ref "U$9") (pin "P$9") (pinfunction "VCOM_P$9") (pintype "bidirectional"))
    )
    (net (code "56") (name "Net-(C40-Pad2)") (class "Default")
      (node (ref "C40") (pin "2") (pinfunction "2_2") (pintype "passive"))
      (node (ref "R26") (pin "2") (pinfunction "2_2") (pintype "passive"))
    )
    (net (code "57") (name "Net-(C41-Pad2)") (class "Default")
      (node (ref "C41") (pin "2") (pinfunction "2_2") (pintype "passive"))
      (node (ref "R27") (pin "2") (pinfunction "2_2") (pintype "passive"))
    )
    (net (code "58") (name "Net-(D1-PadAN)") (class "Default")
      (node (ref "D1") (pin "AN") (pinfunction "AN_AN") (pintype "bidirectional"))
      (node (ref "R3") (pin "2") (pinfunction "2_2") (pintype "passive"))
    )
    (net (code "59") (name "Net-(D2-PadAN)") (class "Default")
      (node (ref "D2") (pin "AN") (pinfunction "AN_AN") (pintype "bidirectional"))
      (node (ref "R45") (pin "2") (pinfunction "2_2") (pintype "passive"))
    )
    (net (code "60") (name "Net-(D3-PadAN)") (class "Default")
      (node (ref "D3") (pin "AN") (pinfunction "AN_AN") (pintype "bidirectional"))
      (node (ref "R46") (pin "2") (pinfunction "2_2") (pintype "passive"))
    )
    (net (code "61") (name "Net-(D4-PadAN)") (class "Default")
      (node (ref "D4") (pin "AN") (pinfunction "AN_AN") (pintype "bidirectional"))
      (node (ref "R47") (pin "2") (pinfunction "2_2") (pintype "passive"))
    )
    (net (code "62") (name "Net-(J3-D_N)") (class "Default")
      (node (ref "J3") (pin "P$2") (pinfunction "D_N_P$2") (pintype "bidirectional"))
      (node (ref "U$7") (pin "P$5") (pinfunction "D-_P$5") (pintype "bidirectional"))
    )
    (net (code "63") (name "Net-(J3-D_P)") (class "Default")
      (node (ref "J3") (pin "P$3") (pinfunction "D_P_P$3") (pintype "bidirectional"))
      (node (ref "U$7") (pin "P$4") (pinfunction "D+_P$4") (pintype "bidirectional"))
    )
    (net (code "64") (name "Net-(J4-Pad15)") (class "Default")
      (node (ref "J4") (pin "15") (pinfunction "15_15") (pintype "passive"))
      (node (ref "SB5") (pin "P$2") (pinfunction "P$2_P$2") (pintype "bidirectional"))
    )
    (net (code "65") (name "Net-(J5-D_N)") (class "Default")
      (node (ref "J5") (pin "P$2") (pinfunction "D_N_P$2") (pintype "bidirectional"))
      (node (ref "R14") (pin "2") (pinfunction "2_2") (pintype "passive"))
    )
    (net (code "66") (name "Net-(J5-D_P)") (class "Default")
      (node (ref "J5") (pin "P$3") (pinfunction "D_P_P$3") (pintype "bidirectional"))
      (node (ref "R13") (pin "2") (pinfunction "2_2") (pintype "passive"))
    )
    (net (code "67") (name "Net-(J5-VBUS)") (class "Default")
      (node (ref "J5") (pin "P$1") (pinfunction "VBUS_P$1") (pintype "bidirectional"))
      (node (ref "R15") (pin "2") (pinfunction "2_2") (pintype "passive"))
    )
    (net (code "68") (name "Net-(R7-Pad2)") (class "Default")
      (node (ref "R7") (pin "2") (pinfunction "2_2") (pintype "passive"))
      (node (ref "U$4") (pin "P$31") (pinfunction "P$31_P$31") (pintype "bidirectional"))
    )
    (net (code "69") (name "Net-(SPKR0-PadTP)") (class "Default")
      (node (ref "SPKR0") (pin "TP") (pinfunction "TP_TP") (pintype "input"))
      (node (ref "U$6") (pin "NEG") (pinfunction "NEG_NEG") (pintype "bidirectional"))
    )
    (net (code "70") (name "Net-(SPRK1-PadTP)") (class "Default")
      (node (ref "SPRK1") (pin "TP") (pinfunction "TP_TP") (pintype "input"))
      (node (ref "U$8") (pin "NEG") (pinfunction "NEG_NEG") (pintype "bidirectional"))
    )
    (net (code "71") (name "Net-(U$1-PB12A)") (class "Default")
      (node (ref "SB1") (pin "P$2") (pinfunction "P$2_P$2") (pintype "bidirectional"))
      (node (ref "U$1") (pin "P$40") (pinfunction "PB12A_P$40") (pintype "bidirectional"))
    )
    (net (code "72") (name "Net-(U$1-PB12B)") (class "Default")
      (node (ref "SB2") (pin "P$2") (pinfunction "P$2_P$2") (pintype "bidirectional"))
      (node (ref "U$1") (pin "P$41") (pinfunction "PB12B_P$41") (pintype "bidirectional"))
    )
    (net (code "73") (name "Net-(U$1-PB12C)") (class "Default")
      (node (ref "SB3") (pin "P$2") (pinfunction "P$2_P$2") (pintype "bidirectional"))
      (node (ref "U$1") (pin "P$42") (pinfunction "PB12C_P$42") (pintype "bidirectional"))
    )
    (net (code "74") (name "Net-(U$1-PB12D)") (class "Default")
      (node (ref "SB4") (pin "P$2") (pinfunction "P$2_P$2") (pintype "bidirectional"))
      (node (ref "U$1") (pin "P$43") (pinfunction "PB12D_P$43") (pintype "bidirectional"))
    )
    (net (code "75") (name "Net-(U$1-PT10C{slash}JTAGENB)") (class "Default")
      (node (ref "R17") (pin "2") (pinfunction "2_2") (pintype "passive"))
      (node (ref "U$1") (pin "P$82") (pinfunction "PT10C/JTAGENB_P$82") (pintype "bidirectional"))
    )
    (net (code "76") (name "Net-(U$2-AIN1L)") (class "Default")
      (node (ref "R1") (pin "1") (pinfunction "1_1") (pintype "passive"))
      (node (ref "U$2") (pin "19") (pinfunction "AIN1R_19") (pintype "bidirectional"))
      (node (ref "U$2") (pin "20") (pinfunction "AIN1L_20") (pintype "bidirectional"))
    )
    (net (code "77") (name "Net-(U$2-HPOL{slash}LOL)") (class "Default")
      (node (ref "U$2") (pin "15") (pinfunction "HPOL/LOL_15") (pintype "bidirectional"))
      (node (ref "U$6") (pin "POS") (pinfunction "POS_POS") (pintype "bidirectional"))
    )
    (net (code "78") (name "Net-(U$2-HPOR{slash}LOR)") (class "Default")
      (node (ref "U$2") (pin "14") (pinfunction "HPOR/LOR_14") (pintype "bidirectional"))
      (node (ref "U$8") (pin "POS") (pinfunction "POS_POS") (pintype "bidirectional"))
    )
    (net (code "79") (name "Net-(U$2-MODE)") (class "Default")
      (node (ref "R6") (pin "2") (pinfunction "2_2") (pintype "passive"))
      (node (ref "U$2") (pin "1") (pinfunction "MODE_1") (pintype "bidirectional"))
    )
    (net (code "80") (name "Net-(U$2-VCOM)") (class "Default")
      (node (ref "C20") (pin "1") (pinfunction "1_1") (pintype "passive"))
      (node (ref "U$2") (pin "16") (pinfunction "VCOM_16") (pintype "bidirectional"))
    )
    (net (code "81") (name "Net-(U$5-DRAIN)") (class "Default")
      (node (ref "U$4") (pin "P$33") (pinfunction "P$33_P$33") (pintype "bidirectional"))
      (node (ref "U$4") (pin "P$34") (pinfunction "P$34_P$34") (pintype "bidirectional"))
      (node (ref "U$4") (pin "P$35") (pinfunction "P$35_P$35") (pintype "bidirectional"))
      (node (ref "U$4") (pin "P$36") (pinfunction "P$36_P$36") (pintype "bidirectional"))
      (node (ref "U$4") (pin "P$37") (pinfunction "P$37_P$37") (pintype "bidirectional"))
      (node (ref "U$5") (pin "P$3") (pinfunction "DRAIN_P$3") (pintype "bidirectional"))
    )
    (net (code "82") (name "Net-(U$5-GATE)") (class "Default")
      (node (ref "R19") (pin "1") (pinfunction "1_1") (pintype "passive"))
      (node (ref "U$5") (pin "P$1") (pinfunction "GATE_P$1") (pintype "bidirectional"))
    )
    (net (code "83") (name "Net-(U$5-SOURCE)") (class "Default")
      (node (ref "R18") (pin "2") (pinfunction "2_2") (pintype "passive"))
      (node (ref "U$5") (pin "P$2") (pinfunction "SOURCE_P$2") (pintype "bidirectional"))
    )
    (net (code "84") (name "Net-(U$7-~{RST})") (class "Default")
      (node (ref "R2") (pin "1") (pinfunction "1_1") (pintype "passive"))
      (node (ref "U$7") (pin "P$9") (pinfunction "~{RST}_P$9") (pintype "bidirectional"))
    )
    (net (code "85") (name "Net-(U$7-~{SUSPEND})") (class "Default")
      (node (ref "R3") (pin "1") (pinfunction "1_1") (pintype "passive"))
      (node (ref "U$7") (pin "P$11") (pinfunction "~{SUSPEND}_P$11") (pintype "bidirectional"))
    )
    (net (code "86") (name "Net-(U$9-ADR1)") (class "Default")
      (node (ref "R32") (pin "1") (pinfunction "1_1") (pintype "passive"))
      (node (ref "U$9") (pin "P$24") (pinfunction "ADR1_P$24") (pintype "bidirectional"))
    )
    (net (code "87") (name "Net-(U$9-MODE)") (class "Default")
      (node (ref "R31") (pin "1") (pinfunction "1_1") (pintype "passive"))
      (node (ref "U$9") (pin "P$20") (pinfunction "MODE_P$20") (pintype "bidirectional"))
    )
    (net (code "88") (name "Net-(U$9-MS{slash}ADR0)") (class "Default")
      (node (ref "R33") (pin "1") (pinfunction "1_1") (pintype "passive"))
      (node (ref "U$9") (pin "P$23") (pinfunction "MS/ADR0_P$23") (pintype "bidirectional"))
    )
    (net (code "89") (name "Net-(U$9-VOUTR+)") (class "Default")
      (node (ref "C40") (pin "1") (pinfunction "1_1") (pintype "passive"))
      (node (ref "U$9") (pin "P$13") (pinfunction "VOUTR+_P$13") (pintype "bidirectional"))
    )
    (net (code "90") (name "Net-(U$9-VOUTR-)") (class "Default")
      (node (ref "C41") (pin "1") (pinfunction "1_1") (pintype "passive"))
      (node (ref "U$9") (pin "P$14") (pinfunction "VOUTR-_P$14") (pintype "bidirectional"))
    )
    (net (code "91") (name "Net-(U$10-C1N)") (class "Default")
      (node (ref "C44") (pin "2") (pinfunction "2_2") (pintype "passive"))
      (node (ref "U$10") (pin "P$15") (pinfunction "C1N_P$15") (pintype "bidirectional"))
    )
    (net (code "92") (name "Net-(U$10-C1P)") (class "Default")
      (node (ref "C44") (pin "1") (pinfunction "1_1") (pintype "passive"))
      (node (ref "U$10") (pin "P$16") (pinfunction "C1P_P$16") (pintype "bidirectional"))
    )
    (net (code "93") (name "Net-(U$10-FB+)") (class "Default")
      (node (ref "R28") (pin "2") (pinfunction "2_2") (pintype "passive"))
      (node (ref "U$10") (pin "P$12") (pinfunction "FB+_P$12") (pintype "bidirectional"))
    )
    (net (code "94") (name "Net-(U$10-FB-)") (class "Default")
      (node (ref "R29") (pin "2") (pinfunction "2_2") (pintype "passive"))
      (node (ref "U$10") (pin "P$9") (pinfunction "FB-_P$9") (pintype "bidirectional"))
    )
    (net (code "95") (name "Net-(U$10-IN+)") (class "Default")
      (node (ref "R26") (pin "1") (pinfunction "1_1") (pintype "passive"))
      (node (ref "R28") (pin "1") (pinfunction "1_1") (pintype "passive"))
      (node (ref "U$10") (pin "P$11") (pinfunction "IN+_P$11") (pintype "bidirectional"))
    )
    (net (code "96") (name "Net-(U$10-IN-)") (class "Default")
      (node (ref "R27") (pin "1") (pinfunction "1_1") (pintype "passive"))
      (node (ref "R29") (pin "1") (pinfunction "1_1") (pintype "passive"))
      (node (ref "U$10") (pin "P$10") (pinfunction "IN-_P$10") (pintype "bidirectional"))
    )
    (net (code "97") (name "Net-(U$10-OUT+)") (class "Default")
      (node (ref "SPK2+") (pin "TP") (pinfunction "TP_TP") (pintype "input"))
      (node (ref "U$10") (pin "P$4") (pinfunction "OUT+_P$4") (pintype "bidirectional"))
    )
    (net (code "98") (name "Net-(U$10-OUT-)") (class "Default")
      (node (ref "SPK2-") (pin "TP") (pinfunction "TP_TP") (pintype "input"))
      (node (ref "U$10") (pin "P$5") (pinfunction "OUT-_P$5") (pintype "bidirectional"))
    )
    (net (code "99") (name "Net-(U1-ADVREF)") (class "Default")
      (node (ref "U1") (pin "P$1") (pinfunction "ADVREF_P$1") (pintype "bidirectional"))
      (node (ref "VREF") (pin "TP") (pinfunction "TP_TP") (pintype "input"))
    )
    (net (code "100") (name "Net-(U1-PA15{slash}PGMD3)") (class "Default")
      (node (ref "R23") (pin "2") (pinfunction "2_2") (pintype "passive"))
      (node (ref "U1") (pin "P$20") (pinfunction "PA15/PGMD3_P$20") (pintype "bidirectional"))
    )
    (net (code "101") (name "Net-(U1-PA16{slash}PGMD4)") (class "Default")
      (node (ref "R22") (pin "2") (pinfunction "2_2") (pintype "passive"))
      (node (ref "U1") (pin "P$19") (pinfunction "PA16/PGMD4_P$19") (pintype "bidirectional"))
    )
    (net (code "102") (name "Net-(U1-PA17{slash}PGMD5{slash}AD0)") (class "Default")
      (node (ref "R21") (pin "2") (pinfunction "2_2") (pintype "passive"))
      (node (ref "U1") (pin "P$9") (pinfunction "PA17/PGMD5/AD0_P$9") (pintype "bidirectional"))
    )
    (net (code "103") (name "Net-(U1-PA18{slash}PGMD6{slash}AD1)") (class "Default")
      (node (ref "AD1") (pin "TP") (pinfunction "TP_TP") (pintype "input"))
      (node (ref "U1") (pin "P$10") (pinfunction "PA18/PGMD6/AD1_P$10") (pintype "bidirectional"))
    )
    (net (code "104") (name "Net-(U1-PA31)") (class "Default")
      (node (ref "R12") (pin "1") (pinfunction "1_1") (pintype "passive"))
      (node (ref "U1") (pin "P$52") (pinfunction "PA31_P$52") (pintype "bidirectional"))
    )
    (net (code "105") (name "Net-(U1-PB13{slash}DAC0)") (class "Default")
      (node (ref "R25") (pin "1") (pinfunction "1_1") (pintype "passive"))
      (node (ref "U1") (pin "P$59") (pinfunction "PB13/DAC0_P$59") (pintype "bidirectional"))
    )
    (net (code "106") (name "Net-(U1-VDDPLL)") (class "Default")
      (node (ref "C14") (pin "1") (pinfunction "1_1") (pintype "passive"))
      (node (ref "U1") (pin "P$64") (pinfunction "VDDPLL_P$64") (pintype "bidirectional"))
    )
    (net (code "107") (name "Net-(U1-XIN{slash}PGMCK{slash}PB9)") (class "Default")
      (node (ref "C2") (pin "1") (pinfunction "1_1") (pintype "passive"))
      (node (ref "U$3") (pin "P$1") (pinfunction "P$1_P$1") (pintype "bidirectional"))
      (node (ref "U1") (pin "P$62") (pinfunction "XIN/PGMCK/PB9_P$62") (pintype "bidirectional"))
    )
    (net (code "108") (name "Net-(U1-XOUT{slash}PB8)") (class "Default")
      (node (ref "C3") (pin "1") (pinfunction "1_1") (pintype "passive"))
      (node (ref "U$3") (pin "P$3") (pinfunction "P$3_P$3") (pintype "bidirectional"))
      (node (ref "U1") (pin "P$61") (pinfunction "XOUT/PB8_P$61") (pintype "bidirectional"))
    )
    (net (code "109") (name "PCM1789_MUTE") (class "Default")
      (node (ref "R30") (pin "1") (pinfunction "1_1") (pintype "passive"))
      (node (ref "U$9") (pin "P$17") (pinfunction "AMUTEI_P$17") (pintype "bidirectional"))
    )
    (net (code "110") (name "PCM_17XX_SYSCLK") (class "Default")
      (node (ref "R25") (pin "2") (pinfunction "2_2") (pintype "passive"))
      (node (ref "U$2") (pin "9") (pinfunction "SCKI_9") (pintype "bidirectional"))
      (node (ref "U$9") (pin "P$5") (pinfunction "SCKI_P$5") (pintype "bidirectional"))
    )
    (net (code "111") (name "SAM4S_NRST") (class "Default")
      (node (ref "J1") (pin "P$10") (pinfunction "~{RESET}_P$10") (pintype "bidirectional"))
      (node (ref "R24") (pin "1") (pinfunction "1_1") (pintype "passive"))
      (node (ref "SW7") (pin "P$3") (pinfunction "P$3_P$3") (pintype "bidirectional"))
      (node (ref "SW7") (pin "P$4") (pinfunction "P$4_P$4") (pintype "bidirectional"))
      (node (ref "U$9") (pin "P$4") (pinfunction "~{RST}_P$4") (pintype "bidirectional"))
      (node (ref "U1") (pin "P$39") (pinfunction "NRST_P$39") (pintype "bidirectional"))
    )
    (net (code "112") (name "SWCLK") (class "Default")
      (node (ref "J1") (pin "P$4") (pinfunction "SWDCLK/TCLK_P$4") (pintype "bidirectional"))
      (node (ref "U1") (pin "P$53") (pinfunction "TCK/SWCLK/PB7_P$53") (pintype "bidirectional"))
    )
    (net (code "113") (name "SWDIO") (class "Default")
      (node (ref "J1") (pin "P$2") (pinfunction "SDWIO/TMS_P$2") (pintype "bidirectional"))
      (node (ref "U1") (pin "P$51") (pinfunction "TMS/SWDIO/PB6_P$51") (pintype "bidirectional"))
    )
    (net (code "114") (name "SWO{slash}TDO") (class "Default")
      (node (ref "J1") (pin "P$6") (pinfunction "SWO/TDO_P$6") (pintype "bidirectional"))
      (node (ref "U1") (pin "P$49") (pinfunction "TDO/TRACESWO/PB5_P$49") (pintype "bidirectional"))
    )
    (net (code "115") (name "SW_1") (class "Default")
      (node (ref "R34") (pin "2") (pinfunction "2_2") (pintype "passive"))
      (node (ref "SW1") (pin "P$3") (pinfunction "P$3_P$3") (pintype "bidirectional"))
      (node (ref "SW1") (pin "P$4") (pinfunction "P$4_P$4") (pintype "bidirectional"))
      (node (ref "U$1") (pin "P$14") (pinfunction "PL5C_P$14") (pintype "bidirectional"))
    )
    (net (code "116") (name "SW_2") (class "Default")
      (node (ref "R35") (pin "2") (pinfunction "2_2") (pintype "passive"))
      (node (ref "SW2") (pin "P$3") (pinfunction "P$3_P$3") (pintype "bidirectional"))
      (node (ref "SW2") (pin "P$4") (pinfunction "P$4_P$4") (pintype "bidirectional"))
      (node (ref "U$1") (pin "P$15") (pinfunction "PL5D_P$15") (pintype "bidirectional"))
    )
    (net (code "117") (name "SW_3") (class "Default")
      (node (ref "R36") (pin "2") (pinfunction "2_2") (pintype "passive"))
      (node (ref "SW3") (pin "P$3") (pinfunction "P$3_P$3") (pintype "bidirectional"))
      (node (ref "SW3") (pin "P$4") (pinfunction "P$4_P$4") (pintype "bidirectional"))
      (node (ref "U$1") (pin "P$16") (pinfunction "PL6A_P$16") (pintype "bidirectional"))
    )
    (net (code "118") (name "SW_4") (class "Default")
      (node (ref "R37") (pin "2") (pinfunction "2_2") (pintype "passive"))
      (node (ref "SW4") (pin "P$3") (pinfunction "P$3_P$3") (pintype "bidirectional"))
      (node (ref "SW4") (pin "P$4") (pinfunction "P$4_P$4") (pintype "bidirectional"))
      (node (ref "U$1") (pin "P$17") (pinfunction "PL6B_P$17") (pintype "bidirectional"))
    )
    (net (code "119") (name "SW_5") (class "Default")
      (node (ref "R38") (pin "2") (pinfunction "2_2") (pintype "passive"))
      (node (ref "SW5") (pin "P$3") (pinfunction "P$3_P$3") (pintype "bidirectional"))
      (node (ref "SW5") (pin "P$4") (pinfunction "P$4_P$4") (pintype "bidirectional"))
      (node (ref "U$1") (pin "P$18") (pinfunction "PL6C_P$18") (pintype "bidirectional"))
    )
    (net (code "120") (name "SW_6") (class "Default")
      (node (ref "R39") (pin "2") (pinfunction "2_2") (pintype "passive"))
      (node (ref "SW6") (pin "P$3") (pinfunction "P$3_P$3") (pintype "bidirectional"))
      (node (ref "SW6") (pin "P$4") (pinfunction "P$4_P$4") (pintype "bidirectional"))
      (node (ref "U$1") (pin "P$19") (pinfunction "PL6D_P$19") (pintype "bidirectional"))
    )
    (net (code "121") (name "TWCK0") (class "Default")
      (node (ref "R5") (pin "1") (pinfunction "1_1") (pintype "passive"))
      (node (ref "U$1") (pin "P$86") (pinfunction "PT9C/SCL/PCLKT0_0_P$86") (pintype "bidirectional"))
      (node (ref "U$2") (pin "4") (pinfunction "MC/SCL_4") (pintype "bidirectional"))
      (node (ref "U$9") (pin "P$22") (pinfunction "MC/SCL_P$22") (pintype "bidirectional"))
      (node (ref "U1") (pin "P$36") (pinfunction "PA4/PGMNCMD_P$36") (pintype "bidirectional"))
    )
    (net (code "122") (name "TWD0") (class "Default")
      (node (ref "R4") (pin "1") (pinfunction "1_1") (pintype "passive"))
      (node (ref "U$1") (pin "P$85") (pinfunction "PT9D/SDA/PCLKC0_0_P$85") (pintype "bidirectional"))
      (node (ref "U$2") (pin "3") (pinfunction "MD/SDA_3") (pintype "bidirectional"))
      (node (ref "U$9") (pin "P$21") (pinfunction "MD/SDA_P$21") (pintype "bidirectional"))
      (node (ref "U1") (pin "P$43") (pinfunction "PA3_P$43") (pintype "bidirectional"))
    )
    (net (code "123") (name "URXD0") (class "Default")
      (node (ref "TP_URXDO") (pin "TP") (pinfunction "TP_TP") (pintype "input"))
      (node (ref "U$7") (pin "P$26") (pinfunction "TXD_P$26") (pintype "bidirectional"))
      (node (ref "U1") (pin "P$30") (pinfunction "PA9/PGMM1_P$30") (pintype "bidirectional"))
    )
    (net (code "124") (name "UTXD0") (class "Default")
      (node (ref "TP_UTXD0") (pin "TP") (pinfunction "TP_TP") (pintype "input"))
      (node (ref "U$7") (pin "P$25") (pinfunction "RXD_P$25") (pintype "bidirectional"))
      (node (ref "U1") (pin "P$29") (pinfunction "PA10/PGMM2_P$29") (pintype "bidirectional"))
    )
    (net (code "125") (name "VBUS") (class "Default")
      (node (ref "C17") (pin "1") (pinfunction "1_1") (pintype "passive"))
      (node (ref "C18") (pin "1") (pinfunction "1_1") (pintype "passive"))
      (node (ref "J3") (pin "P$1") (pinfunction "VBUS_P$1") (pintype "bidirectional"))
      (node (ref "U$7") (pin "P$7") (pinfunction "REGIN_P$7") (pintype "bidirectional"))
      (node (ref "U$7") (pin "P$8") (pinfunction "VBUS_P$8") (pintype "bidirectional"))
    )
    (net (code "126") (name "VBUS_DETECT") (class "Default")
      (node (ref "R15") (pin "1") (pinfunction "1_1") (pintype "passive"))
      (node (ref "R16") (pin "2") (pinfunction "2_2") (pintype "passive"))
      (node (ref "U1") (pin "P$38") (pinfunction "PA28_P$38") (pintype "bidirectional"))
    )
    (net (code "127") (name "VDDOUT") (class "Default")
      (node (ref "C11") (pin "1") (pinfunction "1_1") (pintype "passive"))
      (node (ref "C12") (pin "1") (pinfunction "1_1") (pintype "passive"))
      (node (ref "C6") (pin "1") (pinfunction "1_1") (pintype "passive"))
      (node (ref "C7") (pin "1") (pinfunction "1_1") (pintype "passive"))
      (node (ref "C8") (pin "1") (pinfunction "1_1") (pintype "passive"))
      (node (ref "U1") (pin "P$12") (pinfunction "VDDCORE_P$12") (pintype "bidirectional"))
      (node (ref "U1") (pin "P$24") (pinfunction "VDDCORE_P$24") (pintype "bidirectional"))
      (node (ref "U1") (pin "P$54") (pinfunction "VDDCORE_P$54") (pintype "bidirectional"))
      (node (ref "U1") (pin "P$8") (pinfunction "VDDOUT_P$8") (pintype "bidirectional"))
    )
    (net (code "128") (name "V_WALL_WART") (class "Default")
      (node (ref "3.3_V_REG") (pin "P$4") (pinfunction "VIN_P$4") (pintype "bidirectional"))
      (node (ref "5.0_V_REG") (pin "P$4") (pinfunction "VIN_P$4") (pintype "bidirectional"))
      (node (ref "C1") (pin "1") (pinfunction "1_1") (pintype "passive"))
      (node (ref "J2") (pin "PWR") (pinfunction "PWR_PWR") (pintype "bidirectional"))
    )
    (net (code "129") (name "unconnected-(3.3_V_REG-NC-PadP$5)") (class "Default")
      (node (ref "3.3_V_REG") (pin "P$5") (pinfunction "NC_P$5") (pintype "bidirectional"))
    )
    (net (code "130") (name "unconnected-(3.3_V_REG-NC-PadP$8)") (class "Default")
      (node (ref "3.3_V_REG") (pin "P$8") (pinfunction "NC_P$8") (pintype "bidirectional"))
    )
    (net (code "131") (name "unconnected-(5.0_V_REG-NC-PadP$5)") (class "Default")
      (node (ref "5.0_V_REG") (pin "P$5") (pinfunction "NC_P$5") (pintype "bidirectional"))
    )
    (net (code "132") (name "unconnected-(5.0_V_REG-NC-PadP$8)") (class "Default")
      (node (ref "5.0_V_REG") (pin "P$8") (pinfunction "NC_P$8") (pintype "bidirectional"))
    )
    (net (code "133") (name "unconnected-(J1-GNDDET-PadP$9)") (class "Default")
      (node (ref "J1") (pin "P$9") (pinfunction "GNDDET_P$9") (pintype "bidirectional"))
    )
    (net (code "134") (name "unconnected-(J1-KEY-PadP$7)") (class "Default")
      (node (ref "J1") (pin "P$7") (pinfunction "KEY_P$7") (pintype "bidirectional"))
    )
    (net (code "135") (name "unconnected-(J1-NC{slash}TDI-PadP$8)") (class "Default")
      (node (ref "J1") (pin "P$8") (pinfunction "NC/TDI_P$8") (pintype "bidirectional"))
    )
    (net (code "136") (name "unconnected-(J2-PadGNDBREAK)") (class "Default")
      (node (ref "J2") (pin "GNDBREAK") (pinfunction "GNDBREAK_GNDBREAK") (pintype "bidirectional"))
    )
    (net (code "137") (name "unconnected-(J3-ID-PadP$4)") (class "Default")
      (node (ref "J3") (pin "P$4") (pinfunction "ID_P$4") (pintype "bidirectional"))
    )
    (net (code "138") (name "unconnected-(J4-Pad2)") (class "Default")
      (node (ref "J4") (pin "2") (pinfunction "2_2") (pintype "passive"))
    )
    (net (code "139") (name "unconnected-(J4-Pad3)") (class "Default")
      (node (ref "J4") (pin "3") (pinfunction "3_3") (pintype "passive"))
    )
    (net (code "140") (name "unconnected-(J4-Pad17)") (class "Default")
      (node (ref "J4") (pin "17") (pinfunction "17_17") (pintype "passive"))
    )
    (net (code "141") (name "unconnected-(J4-Pad19)") (class "Default")
      (node (ref "J4") (pin "19") (pinfunction "19_19") (pintype "passive"))
    )
    (net (code "142") (name "unconnected-(J5-ID-PadP$4)") (class "Default")
      (node (ref "J5") (pin "P$4") (pinfunction "ID_P$4") (pintype "bidirectional"))
    )
    (net (code "143") (name "unconnected-(U$1-NC-PadP$11)") (class "Default")
      (node (ref "U$1") (pin "P$11") (pinfunction "NC_P$11") (pintype "bidirectional"))
    )
    (net (code "144") (name "unconnected-(U$1-NC-PadP$61)") (class "Default")
      (node (ref "U$1") (pin "P$61") (pinfunction "NC_P$61") (pintype "bidirectional"))
    )
    (net (code "145") (name "unconnected-(U$1-NC-PadP$89)") (class "Default")
      (node (ref "U$1") (pin "P$89") (pinfunction "NC_P$89") (pintype "bidirectional"))
    )
    (net (code "146") (name "unconnected-(U$1-PB4A{slash}CSSPIN-PadP$27)") (class "Default")
      (node (ref "U$1") (pin "P$27") (pinfunction "PB4A/CSSPIN_P$27") (pintype "bidirectional"))
    )
    (net (code "147") (name "unconnected-(U$1-PB4B-PadP$28)") (class "Default")
      (node (ref "U$1") (pin "P$28") (pinfunction "PB4B_P$28") (pintype "bidirectional"))
    )
    (net (code "148") (name "unconnected-(U$1-PB4C-PadP$29)") (class "Default")
      (node (ref "U$1") (pin "P$29") (pinfunction "PB4C_P$29") (pintype "bidirectional"))
    )
    (net (code "149") (name "unconnected-(U$1-PB4D-PadP$30)") (class "Default")
      (node (ref "U$1") (pin "P$30") (pinfunction "PB4D_P$30") (pintype "bidirectional"))
    )
    (net (code "150") (name "unconnected-(U$1-PB6C{slash}PCLKT2_0-PadP$34)") (class "Default")
      (node (ref "U$1") (pin "P$34") (pinfunction "PB6C/PCLKT2_0_P$34") (pintype "bidirectional"))
    )
    (net (code "151") (name "unconnected-(U$1-PB6D{slash}PCLKC2_0-PadP$35)") (class "Default")
      (node (ref "U$1") (pin "P$35") (pinfunction "PB6D/PCLKC2_0_P$35") (pintype "bidirectional"))
    )
    (net (code "152") (name "unconnected-(U$1-PB10A-PadP$36)") (class "Default")
      (node (ref "U$1") (pin "P$36") (pinfunction "PB10A_P$36") (pintype "bidirectional"))
    )
    (net (code "153") (name "unconnected-(U$1-PB10B-PadP$37)") (class "Default")
      (node (ref "U$1") (pin "P$37") (pinfunction "PB10B_P$37") (pintype "bidirectional"))
    )
    (net (code "154") (name "unconnected-(U$1-PB10D{slash}PCLKC2_1-PadP$39)") (class "Default")
      (node (ref "U$1") (pin "P$39") (pinfunction "PB10D/PCLKC2_1_P$39") (pintype "bidirectional"))
    )
    (net (code "155") (name "unconnected-(U$1-PB14A-PadP$45)") (class "Default")
      (node (ref "U$1") (pin "P$45") (pinfunction "PB14A_P$45") (pintype "bidirectional"))
    )
    (net (code "156") (name "unconnected-(U$1-PB14B-PadP$47)") (class "Default")
      (node (ref "U$1") (pin "P$47") (pinfunction "PB14B_P$47") (pintype "bidirectional"))
    )
    (net (code "157") (name "unconnected-(U$1-PL2C{slash}PCLKT3_2-PadP$3)") (class "Default")
      (node (ref "U$1") (pin "P$3") (pinfunction "PL2C/PCLKT3_2_P$3") (pintype "bidirectional"))
    )
    (net (code "158") (name "unconnected-(U$1-PL2D{slash}PCLKC3_2-PadP$4)") (class "Default")
      (node (ref "U$1") (pin "P$4") (pinfunction "PL2D/PCLKC3_2_P$4") (pintype "bidirectional"))
    )
    (net (code "159") (name "unconnected-(U$1-PL3A-PadP$7)") (class "Default")
      (node (ref "U$1") (pin "P$7") (pinfunction "PL3A_P$7") (pintype "bidirectional"))
    )
    (net (code "160") (name "unconnected-(U$1-PL3B-PadP$8)") (class "Default")
      (node (ref "U$1") (pin "P$8") (pinfunction "PL3B_P$8") (pintype "bidirectional"))
    )
    (net (code "161") (name "unconnected-(U$1-PL3C-PadP$9)") (class "Default")
      (node (ref "U$1") (pin "P$9") (pinfunction "PL3C_P$9") (pintype "bidirectional"))
    )
    (net (code "162") (name "unconnected-(U$1-PL3D-PadP$10)") (class "Default")
      (node (ref "U$1") (pin "P$10") (pinfunction "PL3D_P$10") (pintype "bidirectional"))
    )
    (net (code "163") (name "unconnected-(U$1-PL5A{slash}PCLKT3_1-PadP$12)") (class "Default")
      (node (ref "U$1") (pin "P$12") (pinfunction "PL5A/PCLKT3_1_P$12") (pintype "bidirectional"))
    )
    (net (code "164") (name "unconnected-(U$1-PL5B{slash}PCLKC3_1-PadP$13)") (class "Default")
      (node (ref "U$1") (pin "P$13") (pinfunction "PL5B/PCLKC3_1_P$13") (pintype "bidirectional"))
    )
    (net (code "165") (name "unconnected-(U$1-PL7A{slash}PCLKT3_0-PadP$20)") (class "Default")
      (node (ref "U$1") (pin "P$20") (pinfunction "PL7A/PCLKT3_0_P$20") (pintype "bidirectional"))
    )
    (net (code "166") (name "unconnected-(U$1-PL7B{slash}PCLKC3_0-PadP$21)") (class "Default")
      (node (ref "U$1") (pin "P$21") (pinfunction "PL7B/PCLKC3_0_P$21") (pintype "bidirectional"))
    )
    (net (code "167") (name "unconnected-(U$1-PL7D-PadP$25)") (class "Default")
      (node (ref "U$1") (pin "P$25") (pinfunction "PL7D_P$25") (pintype "bidirectional"))
    )
    (net (code "168") (name "unconnected-(U$1-PR5C{slash}PCLKT1_0-PadP$63)") (class "Default")
      (node (ref "U$1") (pin "P$63") (pinfunction "PR5C/PCLKT1_0_P$63") (pintype "bidirectional"))
    )
    (net (code "169") (name "unconnected-(U$1-PR5D{slash}PCLKC1_0-PadP$62)") (class "Default")
      (node (ref "U$1") (pin "P$62") (pinfunction "PR5D/PCLKC1_0_P$62") (pintype "bidirectional"))
    )
    (net (code "170") (name "unconnected-(U$1-PT6A-PadP$99)") (class "Default")
      (node (ref "U$1") (pin "P$99") (pinfunction "PT6A_P$99") (pintype "bidirectional"))
    )
    (net (code "171") (name "unconnected-(U$1-PT6B-PadP$98)") (class "Default")
      (node (ref "U$1") (pin "P$98") (pinfunction "PT6B_P$98") (pintype "bidirectional"))
    )
    (net (code "172") (name "unconnected-(U$1-PT6C-PadP$97)") (class "Default")
      (node (ref "U$1") (pin "P$97") (pinfunction "PT6C_P$97") (pintype "bidirectional"))
    )
    (net (code "173") (name "unconnected-(U$1-PT9A{slash}PCLKT0_1-PadP$88)") (class "Default")
      (node (ref "U$1") (pin "P$88") (pinfunction "PT9A/PCLKT0_1_P$88") (pintype "bidirectional"))
    )
    (net (code "174") (name "unconnected-(U$1-PT9B{slash}PCLKC0_1-PadP$87)") (class "Default")
      (node (ref "U$1") (pin "P$87") (pinfunction "PT9B/PCLKC0_1_P$87") (pintype "bidirectional"))
    )
    (net (code "175") (name "unconnected-(U$1-PT11C{slash}INITN-PadP$77)") (class "Default")
      (node (ref "U$1") (pin "P$77") (pinfunction "PT11C/INITN_P$77") (pintype "bidirectional"))
    )
    (net (code "176") (name "unconnected-(U$1-PT11D{slash}DONE-PadP$76)") (class "Default")
      (node (ref "U$1") (pin "P$76") (pinfunction "PT11D/DONE_P$76") (pintype "bidirectional"))
    )
    (net (code "177") (name "unconnected-(U$2-MS{slash}ADR-Pad2)") (class "Default")
      (node (ref "U$2") (pin "2") (pinfunction "MS/ADR_2") (pintype "bidirectional"))
    )
    (net (code "178") (name "unconnected-(U$4-PadP$2)") (class "Default")
      (node (ref "U$4") (pin "P$2") (pinfunction "P$2_P$2") (pintype "bidirectional"))
    )
    (net (code "179") (name "unconnected-(U$4-PadP$3)") (class "Default")
      (node (ref "U$4") (pin "P$3") (pinfunction "P$3_P$3") (pintype "bidirectional"))
    )
    (net (code "180") (name "unconnected-(U$4-PadP$4)") (class "Default")
      (node (ref "U$4") (pin "P$4") (pinfunction "P$4_P$4") (pintype "bidirectional"))
    )
    (net (code "181") (name "unconnected-(U$4-PadP$5)") (class "Default")
      (node (ref "U$4") (pin "P$5") (pinfunction "P$5_P$5") (pintype "bidirectional"))
    )
    (net (code "182") (name "unconnected-(U$4-PadP$32)") (class "Default")
      (node (ref "U$4") (pin "P$32") (pinfunction "P$32_P$32") (pintype "bidirectional"))
    )
    (net (code "183") (name "unconnected-(U$4-PadP$40)") (class "Default")
      (node (ref "U$4") (pin "P$40") (pinfunction "P$40_P$40") (pintype "bidirectional"))
    )
    (net (code "184") (name "unconnected-(U$7-CTS-PadP$23)") (class "Default")
      (node (ref "U$7") (pin "P$23") (pinfunction "CTS_P$23") (pintype "bidirectional"))
    )
    (net (code "185") (name "unconnected-(U$7-DCD-PadP$1)") (class "Default")
      (node (ref "U$7") (pin "P$1") (pinfunction "DCD_P$1") (pintype "bidirectional"))
    )
    (net (code "186") (name "unconnected-(U$7-DSR-PadP$27)") (class "Default")
      (node (ref "U$7") (pin "P$27") (pinfunction "DSR_P$27") (pintype "bidirectional"))
    )
    (net (code "187") (name "unconnected-(U$7-DTR-PadP$28)") (class "Default")
      (node (ref "U$7") (pin "P$28") (pinfunction "DTR_P$28") (pintype "bidirectional"))
    )
    (net (code "188") (name "unconnected-(U$7-NC-PadP$10)") (class "Default")
      (node (ref "U$7") (pin "P$10") (pinfunction "NC_P$10") (pintype "bidirectional"))
    )
    (net (code "189") (name "unconnected-(U$7-NC-PadP$13)") (class "Default")
      (node (ref "U$7") (pin "P$13") (pinfunction "NC_P$13") (pintype "bidirectional"))
    )
    (net (code "190") (name "unconnected-(U$7-NC-PadP$14)") (class "Default")
      (node (ref "U$7") (pin "P$14") (pinfunction "NC_P$14") (pintype "bidirectional"))
    )
    (net (code "191") (name "unconnected-(U$7-NC-PadP$15)") (class "Default")
      (node (ref "U$7") (pin "P$15") (pinfunction "NC_P$15") (pintype "bidirectional"))
    )
    (net (code "192") (name "unconnected-(U$7-NC-PadP$16)") (class "Default")
      (node (ref "U$7") (pin "P$16") (pinfunction "NC_P$16") (pintype "bidirectional"))
    )
    (net (code "193") (name "unconnected-(U$7-NC-PadP$17)") (class "Default")
      (node (ref "U$7") (pin "P$17") (pinfunction "NC_P$17") (pintype "bidirectional"))
    )
    (net (code "194") (name "unconnected-(U$7-NC-PadP$18)") (class "Default")
      (node (ref "U$7") (pin "P$18") (pinfunction "NC_P$18") (pintype "bidirectional"))
    )
    (net (code "195") (name "unconnected-(U$7-NC-PadP$19)") (class "Default")
      (node (ref "U$7") (pin "P$19") (pinfunction "NC_P$19") (pintype "bidirectional"))
    )
    (net (code "196") (name "unconnected-(U$7-NC-PadP$20)") (class "Default")
      (node (ref "U$7") (pin "P$20") (pinfunction "NC_P$20") (pintype "bidirectional"))
    )
    (net (code "197") (name "unconnected-(U$7-NC-PadP$21)") (class "Default")
      (node (ref "U$7") (pin "P$21") (pinfunction "NC_P$21") (pintype "bidirectional"))
    )
    (net (code "198") (name "unconnected-(U$7-NC-PadP$22)") (class "Default")
      (node (ref "U$7") (pin "P$22") (pinfunction "NC_P$22") (pintype "bidirectional"))
    )
    (net (code "199") (name "unconnected-(U$7-RI-PadP$2)") (class "Default")
      (node (ref "U$7") (pin "P$2") (pinfunction "RI_P$2") (pintype "bidirectional"))
    )
    (net (code "200") (name "unconnected-(U$7-RTS-PadP$24)") (class "Default")
      (node (ref "U$7") (pin "P$24") (pinfunction "RTS_P$24") (pintype "bidirectional"))
    )
    (net (code "201") (name "unconnected-(U$7-SUSPEND-PadP$12)") (class "Default")
      (node (ref "U$7") (pin "P$12") (pinfunction "SUSPEND_P$12") (pintype "bidirectional"))
    )
    (net (code "202") (name "unconnected-(U$9-AMUTEO-PadP$18)") (class "Default")
      (node (ref "U$9") (pin "P$18") (pinfunction "AMUTEO_P$18") (pintype "bidirectional"))
    )
    (net (code "203") (name "unconnected-(U$9-VOUTL+-PadP$12)") (class "Default")
      (node (ref "U$9") (pin "P$12") (pinfunction "VOUTL+_P$12") (pintype "bidirectional"))
    )
    (net (code "204") (name "unconnected-(U$9-VOUTL--PadP$11)") (class "Default")
      (node (ref "U$9") (pin "P$11") (pinfunction "VOUTL-_P$11") (pintype "bidirectional"))
    )
    (net (code "205") (name "unconnected-(U$9-ZERO1-PadP$19)") (class "Default")
      (node (ref "U$9") (pin "P$19") (pinfunction "ZERO1_P$19") (pintype "bidirectional"))
    )
    (net (code "206") (name "unconnected-(U$10-NC-PadP$8)") (class "Default")
      (node (ref "U$10") (pin "P$8") (pinfunction "NC_P$8") (pintype "bidirectional"))
    )
    (net (code "207") (name "unconnected-(U1-ERASE{slash}PB12-PadP$55)") (class "Default")
      (node (ref "U1") (pin "P$55") (pinfunction "ERASE/PB12_P$55") (pintype "bidirectional"))
    )
    (net (code "208") (name "unconnected-(U1-JTAGSEL-PadP$50)") (class "Default")
      (node (ref "U1") (pin "P$50") (pinfunction "JTAGSEL_P$50") (pintype "bidirectional"))
    )
    (net (code "209") (name "unconnected-(U1-PA0{slash}PGMEN0-PadP$48)") (class "Default")
      (node (ref "U1") (pin "P$48") (pinfunction "PA0/PGMEN0_P$48") (pintype "bidirectional"))
    )
    (net (code "210") (name "unconnected-(U1-PA1{slash}PGMEN1-PadP$47)") (class "Default")
      (node (ref "U1") (pin "P$47") (pinfunction "PA1/PGMEN1_P$47") (pintype "bidirectional"))
    )
    (net (code "211") (name "unconnected-(U1-PA19{slash}PGMD7{slash}AD2-PadP$13)") (class "Default")
      (node (ref "U1") (pin "P$13") (pinfunction "PA19/PGMD7/AD2_P$13") (pintype "bidirectional"))
    )
    (net (code "212") (name "unconnected-(U1-PA20{slash}PGMD8{slash}AD3-PadP$16)") (class "Default")
      (node (ref "U1") (pin "P$16") (pinfunction "PA20/PGMD8/AD3_P$16") (pintype "bidirectional"))
    )
    (net (code "213") (name "unconnected-(U1-PA21{slash}PGMD9{slash}AD8-PadP$11)") (class "Default")
      (node (ref "U1") (pin "P$11") (pinfunction "PA21/PGMD9/AD8_P$11") (pintype "bidirectional"))
    )
    (net (code "214") (name "unconnected-(U1-PA22{slash}PGMD10{slash}AD9-PadP$14)") (class "Default")
      (node (ref "U1") (pin "P$14") (pinfunction "PA22/PGMD10/AD9_P$14") (pintype "bidirectional"))
    )
    (net (code "215") (name "unconnected-(U1-PA23{slash}PGMD11-PadP$15)") (class "Default")
      (node (ref "U1") (pin "P$15") (pinfunction "PA23/PGMD11_P$15") (pintype "bidirectional"))
    )
    (net (code "216") (name "unconnected-(U1-PA24{slash}PGMD12-PadP$23)") (class "Default")
      (node (ref "U1") (pin "P$23") (pinfunction "PA24/PGMD12_P$23") (pintype "bidirectional"))
    )
    (net (code "217") (name "unconnected-(U1-PA25{slash}PGMD13-PadP$25)") (class "Default")
      (node (ref "U1") (pin "P$25") (pinfunction "PA25/PGMD13_P$25") (pintype "bidirectional"))
    )
    (net (code "218") (name "unconnected-(U1-PA26{slash}PGMD14-PadP$26)") (class "Default")
      (node (ref "U1") (pin "P$26") (pinfunction "PA26/PGMD14_P$26") (pintype "bidirectional"))
    )
    (net (code "219") (name "unconnected-(U1-PA27{slash}PGMD15-PadP$37)") (class "Default")
      (node (ref "U1") (pin "P$37") (pinfunction "PA27/PGMD15_P$37") (pintype "bidirectional"))
    )
    (net (code "220") (name "unconnected-(U1-PA29-PadP$41)") (class "Default")
      (node (ref "U1") (pin "P$41") (pinfunction "PA29_P$41") (pintype "bidirectional"))
    )
    (net (code "221") (name "unconnected-(U1-PA30-PadP$42)") (class "Default")
      (node (ref "U1") (pin "P$42") (pinfunction "PA30_P$42") (pintype "bidirectional"))
    )
    (net (code "222") (name "unconnected-(U1-PB14{slash}DAC1-PadP$63)") (class "Default")
      (node (ref "U1") (pin "P$63") (pinfunction "PB14/DAC1_P$63") (pintype "bidirectional"))
    )
    (net (code "223") (name "unconnected-(U1-TDI{slash}PB4-PadP$33)") (class "Default")
      (node (ref "U1") (pin "P$33") (pinfunction "TDI/PB4_P$33") (pintype "bidirectional"))
    )
    (net (code "224") (name "unconnected-(U1-TST-PadP$40)") (class "Default")
      (node (ref "U1") (pin "P$40") (pinfunction "TST_P$40") (pintype "bidirectional"))
    )
  )
)
